# ADK_MEGA_2560-REV3.net
KiCad netlist of a schematic drawn in EAGLE
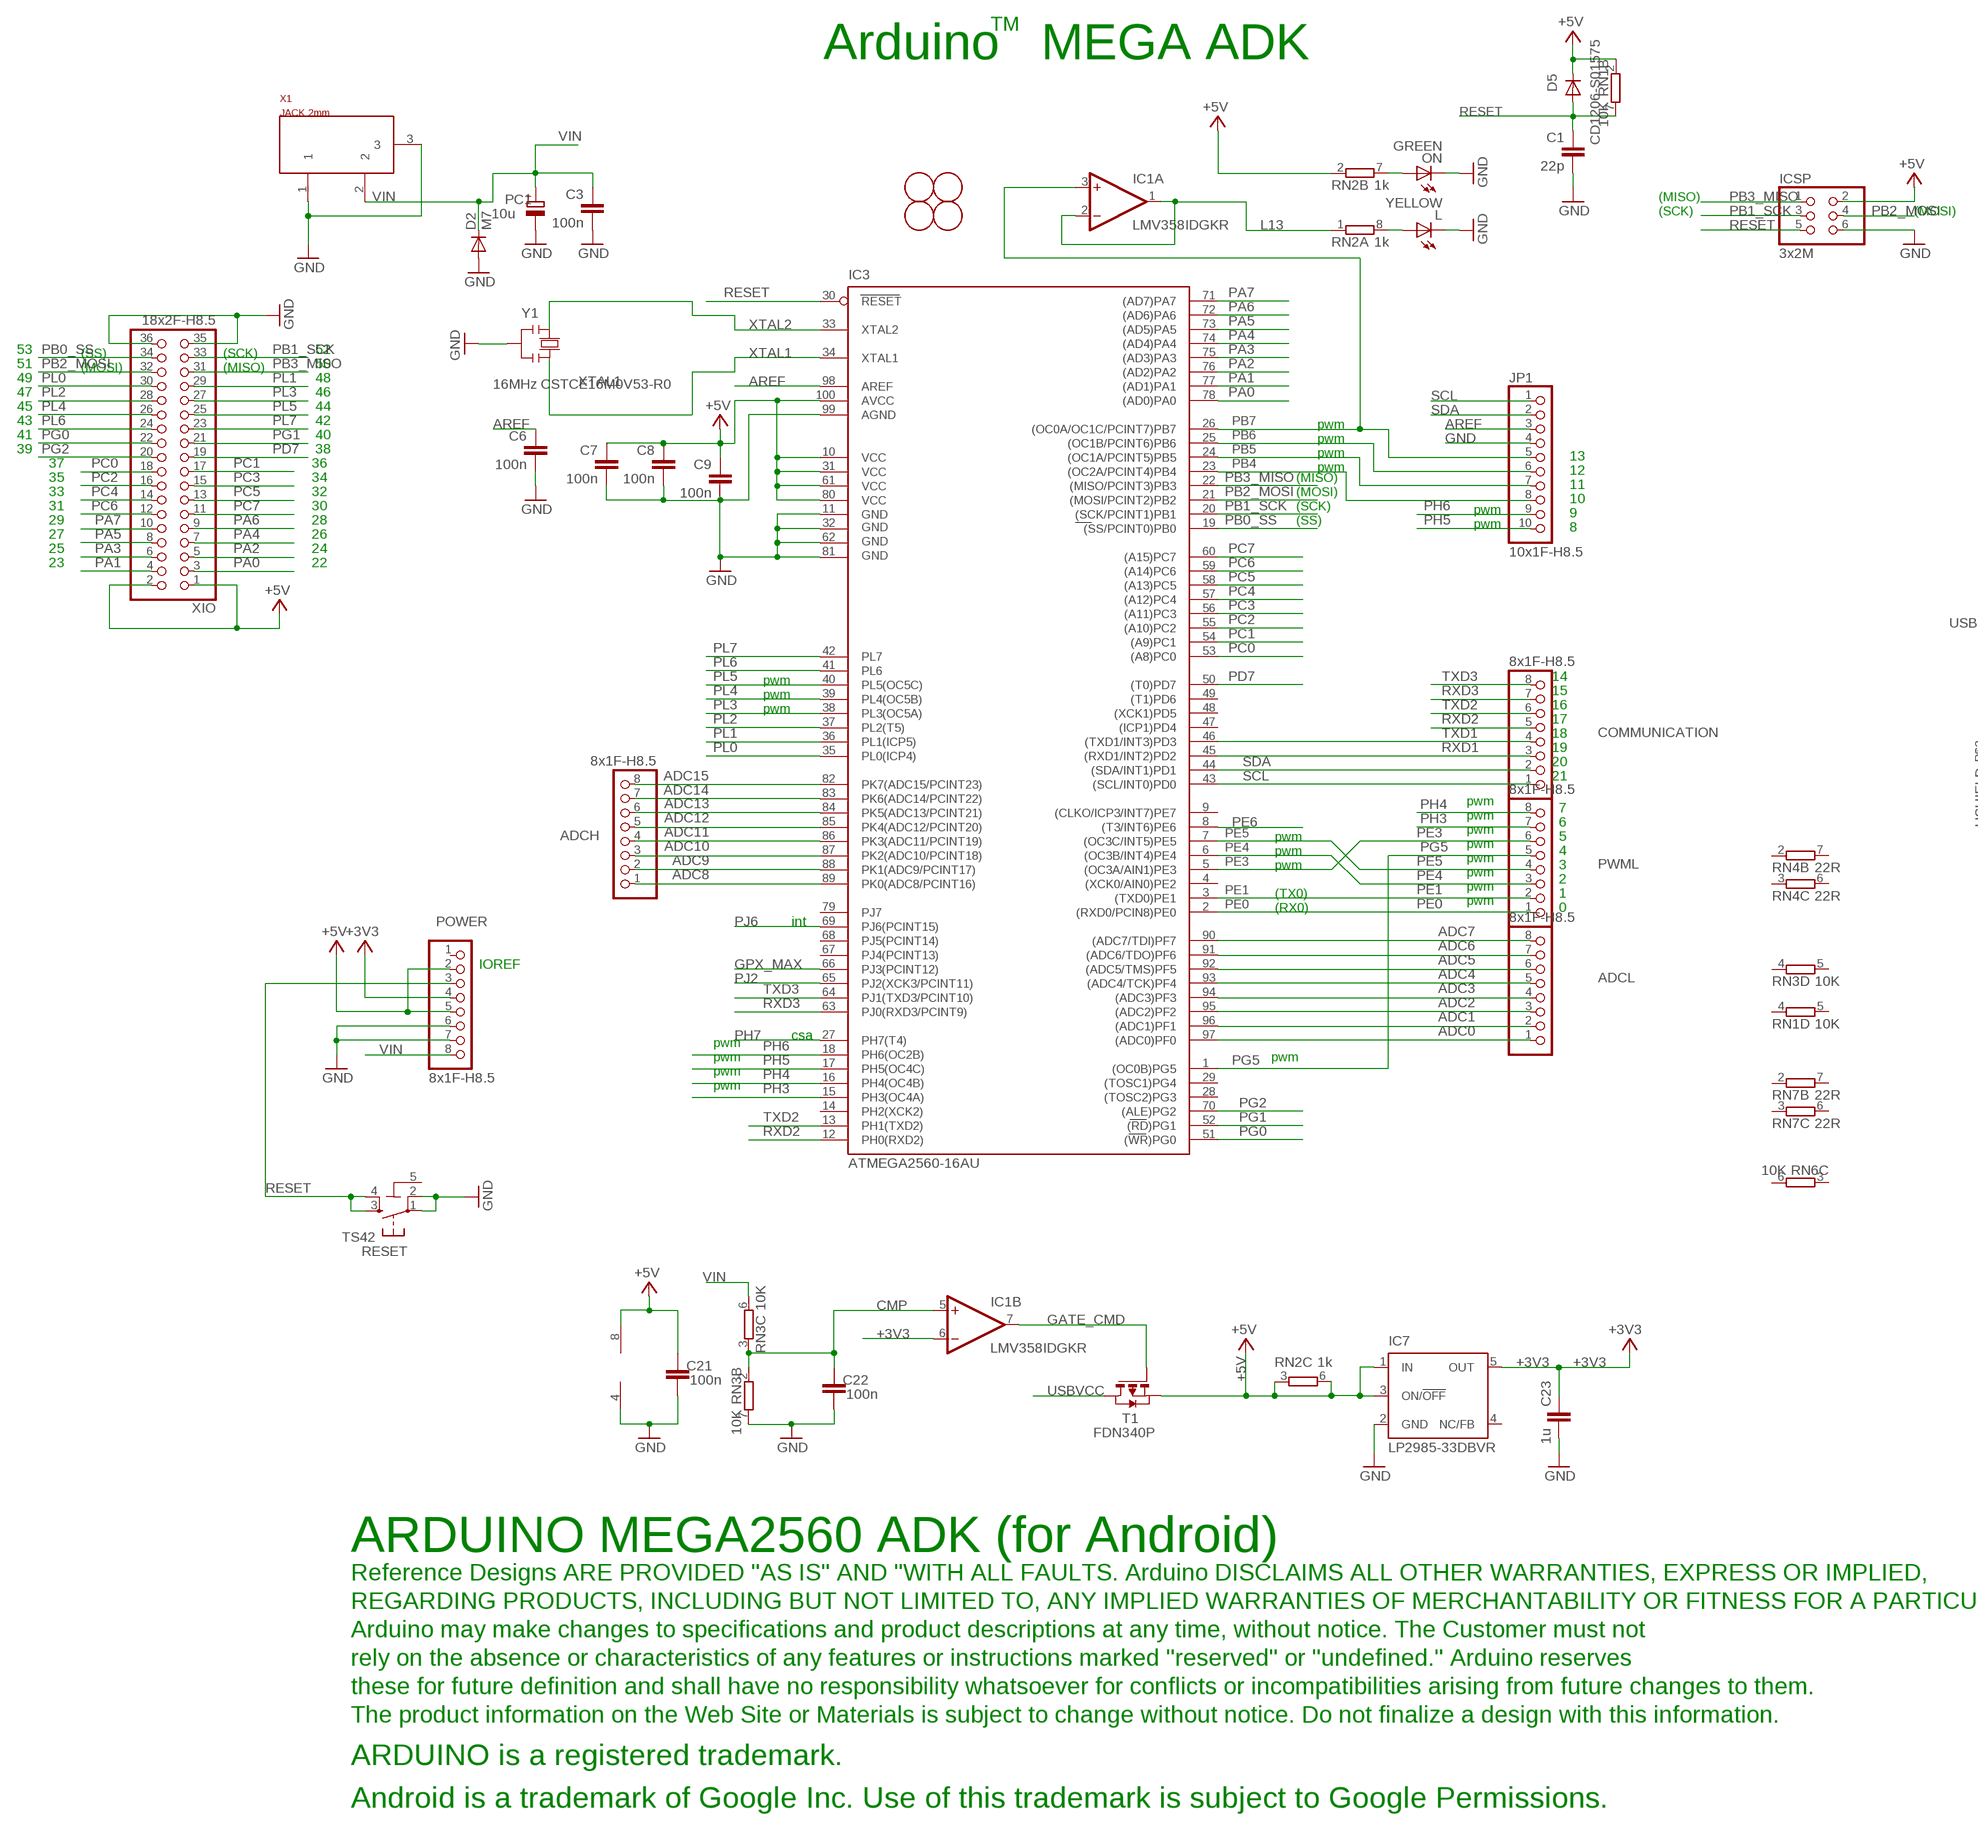
[diagram p0: schematic, sheet 1, part 1 of 2]
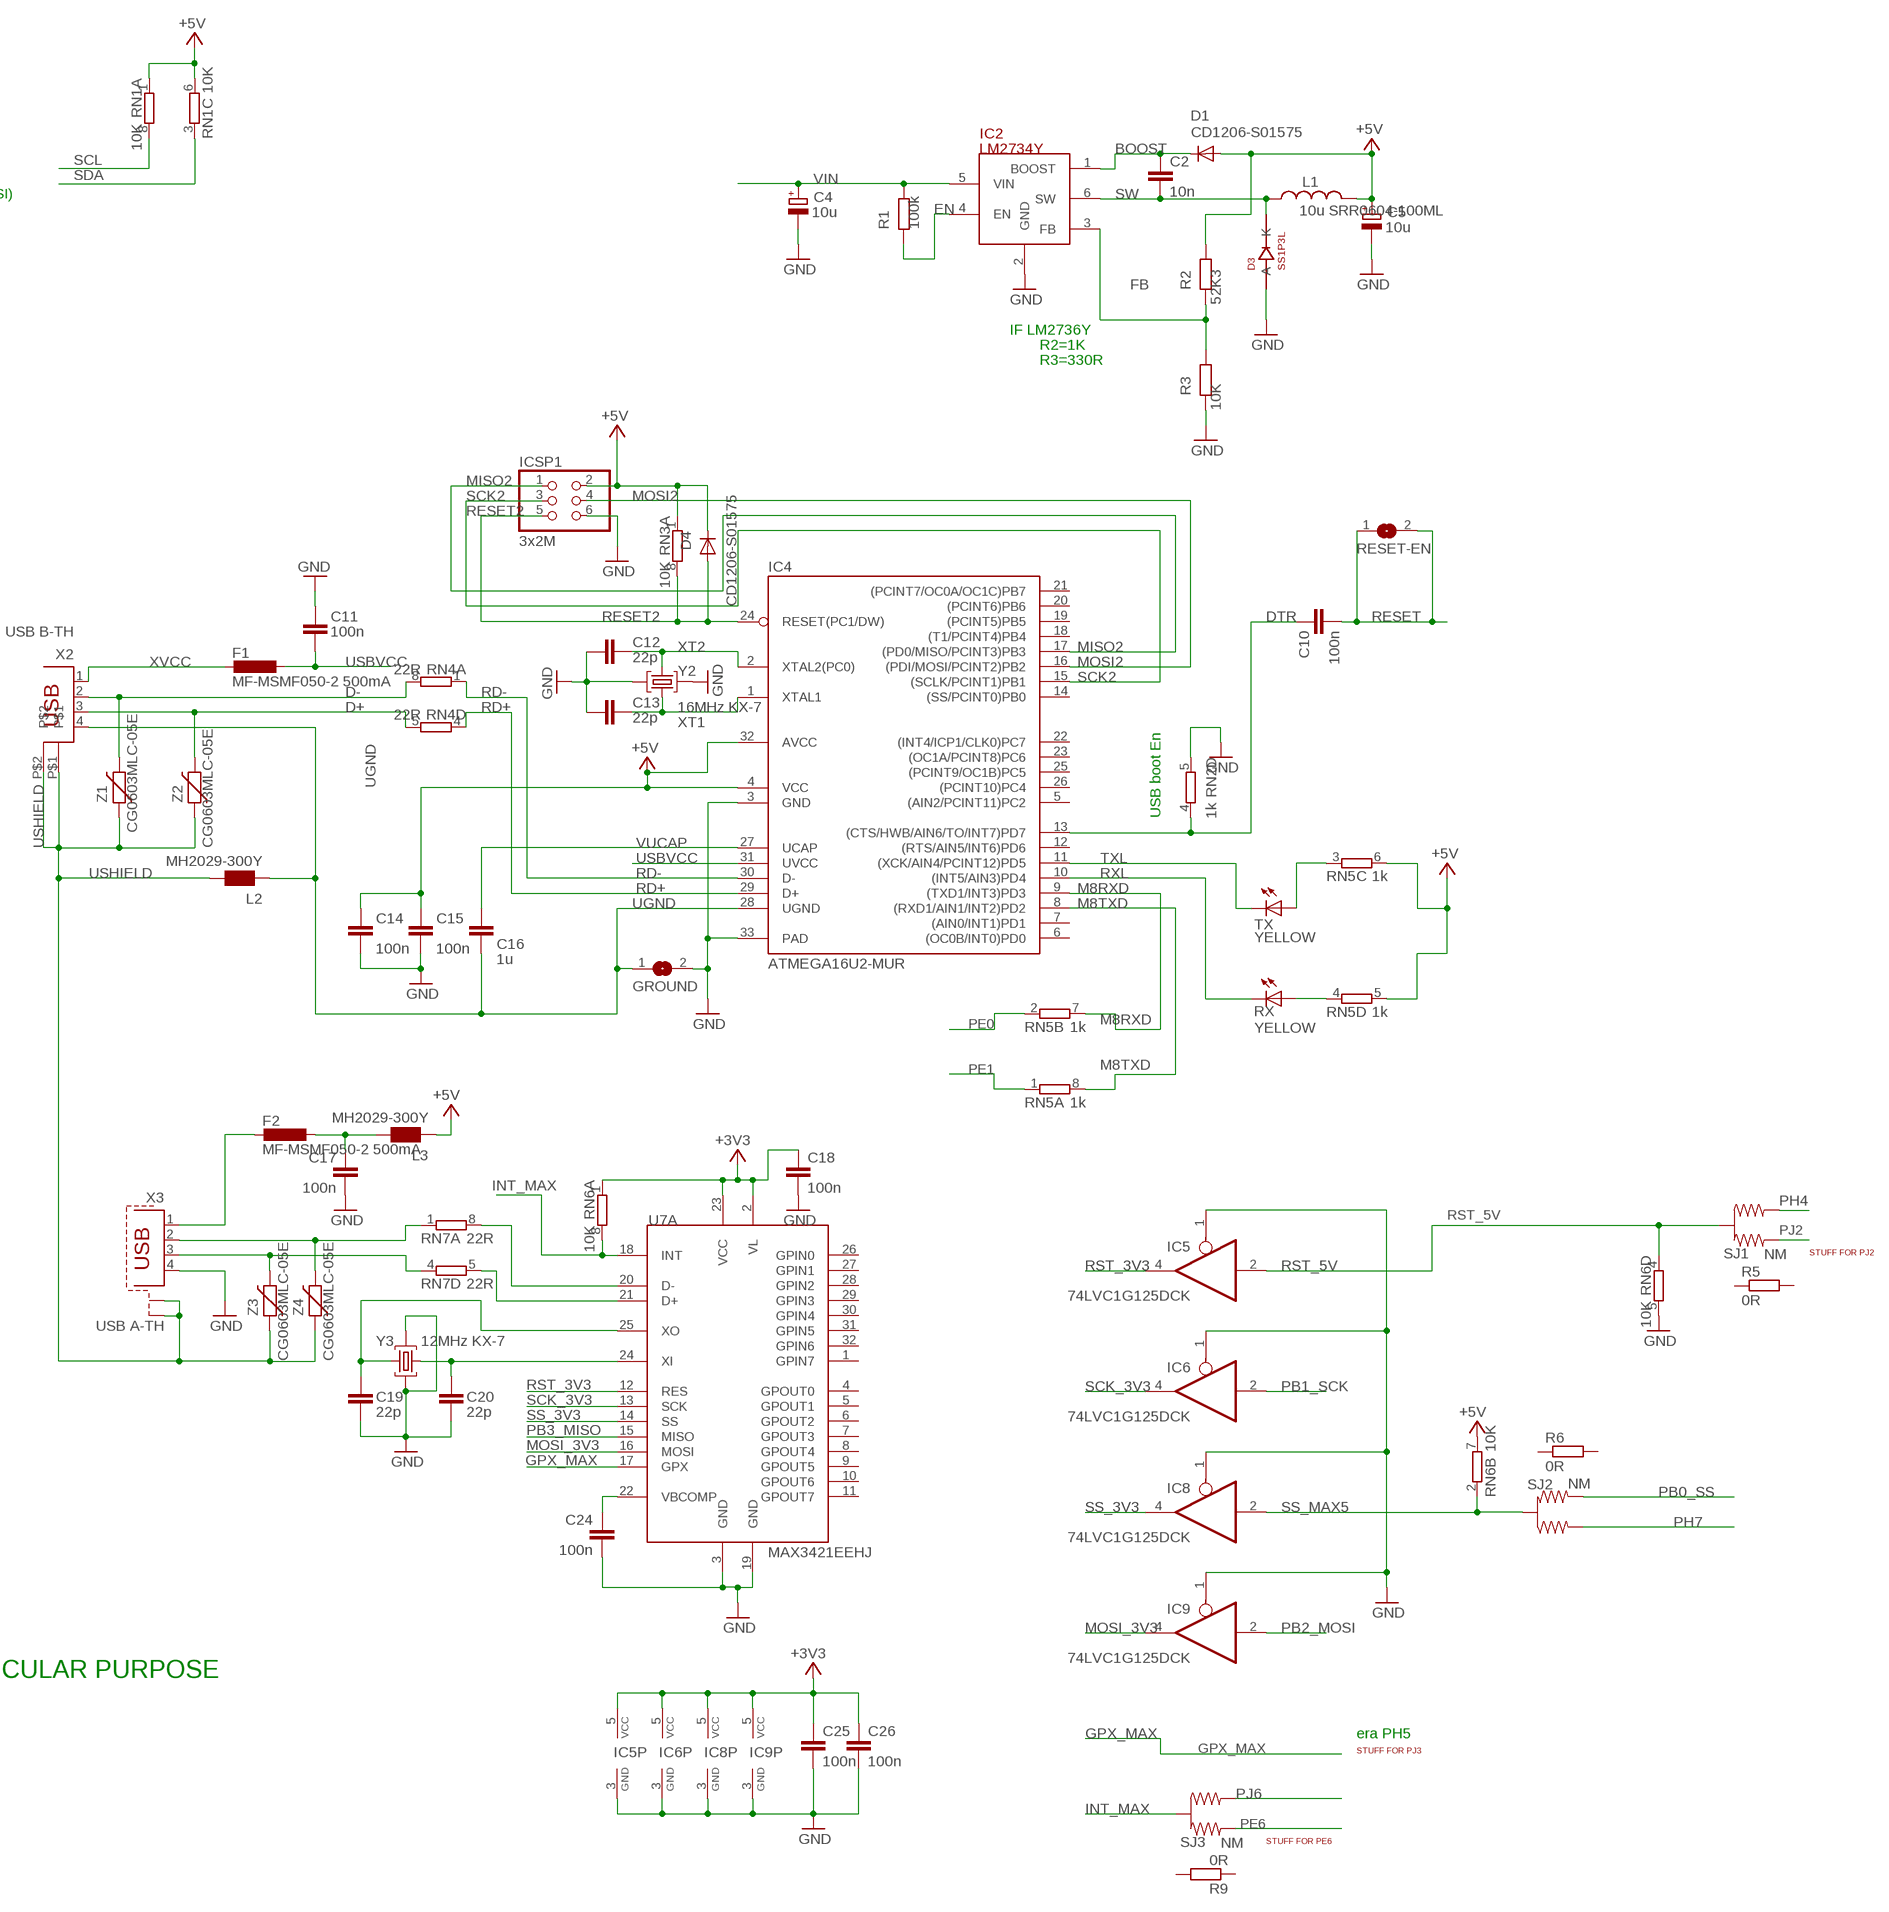
[diagram p1: schematic, sheet 1, part 2 of 2]

(export (version "E")
  (design (tool "Eeschema 10.0.6"))
  (components
    (comp (ref "ADCH")
      (value "8x1F-H8.5")
      (footprint "eagle-import:1X08")
      (libsource (lib "eagle-import") (part "PINHD-1X8"))
    )
    (comp (ref "ADCL")
      (value "8x1F-H8.5")
      (footprint "eagle-import:1X08")
      (libsource (lib "eagle-import") (part "PINHD-1X8"))
    )
    (comp (ref "C1")
      (value "22p")
      (footprint "eagle-import:C0603-ROUND")
      (libsource (lib "eagle-import") (part "C-EU0603-RND"))
    )
    (comp (ref "C2")
      (value "10n")
      (footprint "eagle-import:C0603-ROUND")
      (libsource (lib "eagle-import") (part "C-EUC0603"))
    )
    (comp (ref "C3")
      (value "100n")
      (footprint "eagle-import:C0603-ROUND")
      (libsource (lib "eagle-import") (part "C-EU0603-RND"))
    )
    (comp (ref "C4")
      (value "10u")
      (footprint "eagle-import:SMC_B")
      (libsource (lib "eagle-import") (part "CPOL-EUSMCB"))
    )
    (comp (ref "C5")
      (value "10u")
      (footprint "eagle-import:SMC_B")
      (libsource (lib "eagle-import") (part "CPOL-EUSMCB"))
    )
    (comp (ref "C6")
      (value "100n")
      (footprint "eagle-import:C0603-ROUND")
      (libsource (lib "eagle-import") (part "C-EU0603-RND"))
    )
    (comp (ref "C7")
      (value "100n")
      (footprint "eagle-import:C0603-ROUND")
      (libsource (lib "eagle-import") (part "C-EU0603-RND"))
    )
    (comp (ref "C8")
      (value "100n")
      (footprint "eagle-import:C0603-ROUND")
      (libsource (lib "eagle-import") (part "C-EU0603-RND"))
    )
    (comp (ref "C9")
      (value "100n")
      (footprint "eagle-import:C0603-ROUND")
      (libsource (lib "eagle-import") (part "C-EU0603-RND"))
    )
    (comp (ref "C10")
      (value "100n")
      (footprint "eagle-import:C0603-ROUND")
      (libsource (lib "eagle-import") (part "C-EU0603-RND"))
    )
    (comp (ref "C11")
      (value "100n")
      (footprint "eagle-import:C0603-ROUND")
      (libsource (lib "eagle-import") (part "C-EU0603-RND"))
    )
    (comp (ref "C12")
      (value "22p")
      (footprint "eagle-import:C0603-ROUND")
      (libsource (lib "eagle-import") (part "C-EU0603-RND"))
    )
    (comp (ref "C13")
      (value "22p")
      (footprint "eagle-import:C0603-ROUND")
      (libsource (lib "eagle-import") (part "C-EU0603-RND"))
    )
    (comp (ref "C14")
      (value "100n")
      (footprint "eagle-import:C0603-ROUND")
      (libsource (lib "eagle-import") (part "C-EU0603-RND"))
    )
    (comp (ref "C15")
      (value "100n")
      (footprint "eagle-import:C0603-ROUND")
      (libsource (lib "eagle-import") (part "C-EU0603-RND"))
    )
    (comp (ref "C16")
      (value "1u")
      (footprint "eagle-import:C0603-ROUND")
      (libsource (lib "eagle-import") (part "C-EU0603-RND"))
    )
    (comp (ref "C17")
      (value "100n")
      (footprint "eagle-import:C0603-ROUND")
      (libsource (lib "eagle-import") (part "C-EU0603-RND"))
    )
    (comp (ref "C18")
      (value "100n")
      (footprint "eagle-import:C0603-ROUND")
      (libsource (lib "eagle-import") (part "C-EU0603-RND"))
    )
    (comp (ref "C19")
      (value "22p")
      (footprint "eagle-import:C0603-ROUND")
      (libsource (lib "eagle-import") (part "C-EU0603-RND"))
    )
    (comp (ref "C20")
      (value "22p")
      (footprint "eagle-import:C0603-ROUND")
      (libsource (lib "eagle-import") (part "C-EU0603-RND"))
    )
    (comp (ref "C21")
      (value "100n")
      (footprint "eagle-import:C0603-ROUND")
      (libsource (lib "eagle-import") (part "C-EU0603-RND"))
    )
    (comp (ref "C22")
      (value "100n")
      (footprint "eagle-import:C0603-ROUND")
      (libsource (lib "eagle-import") (part "C-EU0603-RND"))
    )
    (comp (ref "C23")
      (value "1u")
      (footprint "eagle-import:C0603-ROUND")
      (libsource (lib "eagle-import") (part "C-EU0603-RND"))
    )
    (comp (ref "C24")
      (value "100n")
      (footprint "eagle-import:C0603-ROUND")
      (libsource (lib "eagle-import") (part "C-EU0603-RND"))
    )
    (comp (ref "C25")
      (value "100n")
      (footprint "eagle-import:C0603-ROUND")
      (libsource (lib "eagle-import") (part "C-EU0603-RND"))
    )
    (comp (ref "C26")
      (value "100n")
      (footprint "eagle-import:C0603-ROUND")
      (libsource (lib "eagle-import") (part "C-EU0603-RND"))
    )
    (comp (ref "COMMUNICATION")
      (value "8x1F-H8.5")
      (footprint "eagle-import:1X08")
      (libsource (lib "eagle-import") (part "PINHD-1X8"))
    )
    (comp (ref "D1")
      (value "CD1206-S01575")
      (footprint "eagle-import:MINIMELF")
      (libsource (lib "eagle-import") (part "DIODE-MINIMELF"))
    )
    (comp (ref "D2")
      (value "M7")
      (footprint "eagle-import:SMB")
      (libsource (lib "eagle-import") (part "DIODE-SMB"))
    )
    (comp (ref "D3")
      (value "SS1P3L")
      (footprint "eagle-import:DO220AAL")
      (libsource (lib "eagle-import") (part "SS1P3L"))
    )
    (comp (ref "D4")
      (value "CD1206-S01575")
      (footprint "eagle-import:MINIMELF")
      (libsource (lib "eagle-import") (part "DIODE-MINIMELF"))
    )
    (comp (ref "D5")
      (value "CD1206-S01575")
      (footprint "eagle-import:MINIMELF")
      (libsource (lib "eagle-import") (part "DIODE-MINIMELF"))
    )
    (comp (ref "F1")
      (value "MF-MSMF050-2 500mA")
      (footprint "eagle-import:L1812")
      (libsource (lib "eagle-import") (part "L-EUL1812"))
    )
    (comp (ref "F2")
      (value "MF-MSMF050-2 500mA")
      (footprint "eagle-import:L1812")
      (libsource (lib "eagle-import") (part "L-EUL1812"))
    )
    (comp (ref "FID1")
      (value "FIDUCIALMOUNT")
      (footprint "eagle-import:FIDUCIA-MOUNT")
      (libsource (lib "eagle-import") (part "FIDUCIALMOUNT"))
    )
    (comp (ref "FID2")
      (value "FIDUCIALMOUNT")
      (footprint "eagle-import:FIDUCIA-MOUNT")
      (libsource (lib "eagle-import") (part "FIDUCIALMOUNT"))
    )
    (comp (ref "FID3")
      (value "FIDUCIALMOUNT")
      (footprint "eagle-import:FIDUCIA-MOUNT")
      (libsource (lib "eagle-import") (part "FIDUCIALMOUNT"))
    )
    (comp (ref "FID4")
      (value "FIDUCIALMOUNT")
      (footprint "eagle-import:FIDUCIA-MOUNT")
      (libsource (lib "eagle-import") (part "FIDUCIALMOUNT"))
    )
    (comp (ref "GROUND")
      (value "SJ")
      (footprint "eagle-import:SJ")
      (libsource (lib "eagle-import") (part "SJ"))
    )
    (comp (ref "IC1")
      (value "LMV358IDGKR")
      (footprint "eagle-import:MSOP08")
      (libsource (lib "eagle-import") (part "LMV358?MMX"))
    )
    (comp (ref "IC2")
      (value "LM2734Y")
      (footprint "eagle-import:SOT23-6")
      (libsource (lib "eagle-import") (part "LM2736Y"))
    )
    (comp (ref "IC3")
      (value "ATMEGA2560-16AU")
      (footprint "eagle-import:TQFP100")
      (libsource (lib "eagle-import") (part "ATMEGA2560AU2560-16"))
    )
    (comp (ref "IC4")
      (value "ATMEGA16U2-MUR")
      (footprint "eagle-import:MLF32")
      (libsource (lib "eagle-import") (part "ATMEGA16U2-MU"))
    )
    (comp (ref "IC5")
      (value "74LVC1G125DCK")
      (footprint "eagle-import:SC70-5")
      (libsource (lib "eagle-import") (part "741G125DCKLVC"))
    )
    (comp (ref "IC6")
      (value "74LVC1G125DCK")
      (footprint "eagle-import:SC70-5")
      (libsource (lib "eagle-import") (part "741G125DCKLVC"))
    )
    (comp (ref "IC7")
      (value "LP2985-33DBVR")
      (footprint "eagle-import:SOT23-DBV")
      (libsource (lib "eagle-import") (part "LP2985-XXDBVR33"))
    )
    (comp (ref "IC8")
      (value "74LVC1G125DCK")
      (footprint "eagle-import:SC70-5")
      (libsource (lib "eagle-import") (part "741G125DCKLVC"))
    )
    (comp (ref "IC9")
      (value "74LVC1G125DCK")
      (footprint "eagle-import:SC70-5")
      (libsource (lib "eagle-import") (part "741G125DCKLVC"))
    )
    (comp (ref "ICSP")
      (value "3x2M")
      (footprint "eagle-import:2X03")
      (libsource (lib "eagle-import") (part "PINHD-2X3"))
    )
    (comp (ref "ICSP1")
      (value "3x2M")
      (footprint "eagle-import:2X03")
      (libsource (lib "eagle-import") (part "PINHD-2X3"))
    )
    (comp (ref "JP1")
      (value "10x1F-H8.5")
      (footprint "eagle-import:1X10")
      (libsource (lib "eagle-import") (part "PINHD-1X10"))
    )
    (comp (ref "L")
      (value "YELLOW")
      (footprint "eagle-import:CHIP-LED0805")
      (libsource (lib "eagle-import") (part "LEDCHIP-LED0805"))
    )
    (comp (ref "L1")
      (value "10u SRR0604-100ML")
      (footprint "eagle-import:SRR0604")
      (libsource (lib "eagle-import") (part "L-USSRR0604"))
    )
    (comp (ref "L2")
      (value "MH2029-300Y")
      (footprint "eagle-import:0805")
      (libsource (lib "eagle-import") (part "WE-CBF_0805"))
    )
    (comp (ref "L3")
      (value "MH2029-300Y")
      (footprint "eagle-import:0805")
      (libsource (lib "eagle-import") (part "WE-CBF_0805"))
    )
    (comp (ref "ON")
      (value "GREEN")
      (footprint "eagle-import:CHIP-LED0805")
      (libsource (lib "eagle-import") (part "LEDCHIP-LED0805"))
    )
    (comp (ref "PC1")
      (value "10u")
      (footprint "eagle-import:SMC_B")
      (libsource (lib "eagle-import") (part "CPOL-EUSMCB"))
    )
    (comp (ref "POWER")
      (value "8x1F-H8.5")
      (footprint "eagle-import:1X08")
      (libsource (lib "eagle-import") (part "PINHD-1X8"))
    )
    (comp (ref "PWML")
      (value "8x1F-H8.5")
      (footprint "eagle-import:1X08")
      (libsource (lib "eagle-import") (part "PINHD-1X8"))
    )
    (comp (ref "R1")
      (value "100k")
      (footprint "eagle-import:R0603-ROUND")
      (libsource (lib "eagle-import") (part "R-EU_0603-RND"))
    )
    (comp (ref "R2")
      (value "52K3")
      (footprint "eagle-import:R0603-ROUND")
      (libsource (lib "eagle-import") (part "R-EU_0603-RND"))
    )
    (comp (ref "R3")
      (value "10K")
      (footprint "eagle-import:R0603-ROUND")
      (libsource (lib "eagle-import") (part "R-EU_0603-RND"))
    )
    (comp (ref "R5")
      (value "0R")
      (footprint "eagle-import:R0402")
      (libsource (lib "eagle-import") (part "R-EU_R0402"))
    )
    (comp (ref "R6")
      (value "0R")
      (footprint "eagle-import:R0402")
      (libsource (lib "eagle-import") (part "R-EU_R0402"))
    )
    (comp (ref "R9")
      (value "0R")
      (footprint "eagle-import:R0402")
      (libsource (lib "eagle-import") (part "R-EU_R0402"))
    )
    (comp (ref "RESET")
      (value "TS42")
      (footprint "eagle-import:TS42")
      (libsource (lib "eagle-import") (part "TS42"))
    )
    (comp (ref "RESET-EN")
      (value "SJ")
      (footprint "eagle-import:SJ")
      (libsource (lib "eagle-import") (part "SJ"))
    )
    (comp (ref "RN1")
      (value "10K")
      (footprint "eagle-import:CAT16")
      (libsource (lib "eagle-import") (part "4R-NCAT16"))
    )
    (comp (ref "RN2")
      (value "1k")
      (footprint "eagle-import:CAY16")
      (libsource (lib "eagle-import") (part "4R-NCAY16"))
    )
    (comp (ref "RN3")
      (value "10K")
      (footprint "eagle-import:CAT16")
      (libsource (lib "eagle-import") (part "4R-NCAT16"))
    )
    (comp (ref "RN4")
      (value "22R")
      (footprint "eagle-import:CAY16")
      (libsource (lib "eagle-import") (part "4R-NCAY16"))
    )
    (comp (ref "RN5")
      (value "1k")
      (footprint "eagle-import:CAY16")
      (libsource (lib "eagle-import") (part "4R-NCAY16"))
    )
    (comp (ref "RN6")
      (value "10K")
      (footprint "eagle-import:CAT16")
      (libsource (lib "eagle-import") (part "4R-NCAT16"))
    )
    (comp (ref "RN7")
      (value "22R")
      (footprint "eagle-import:CAY16")
      (libsource (lib "eagle-import") (part "4R-NCAY16"))
    )
    (comp (ref "RX")
      (value "YELLOW")
      (footprint "eagle-import:CHIP-LED0805")
      (libsource (lib "eagle-import") (part "LEDCHIP-LED0805"))
    )
    (comp (ref "SJ1")
      (value "NM")
      (footprint "eagle-import:J0402")
      (libsource (lib "eagle-import") (part "J0402"))
    )
    (comp (ref "SJ2")
      (value "NM")
      (footprint "eagle-import:J0402")
      (libsource (lib "eagle-import") (part "J0402"))
    )
    (comp (ref "SJ3")
      (value "NM")
      (footprint "eagle-import:J0402")
      (libsource (lib "eagle-import") (part "J0402"))
    )
    (comp (ref "T1")
      (value "FDN340P")
      (footprint "eagle-import:SOT-23")
      (libsource (lib "eagle-import") (part "PMOSSOT23"))
    )
    (comp (ref "TX")
      (value "YELLOW")
      (footprint "eagle-import:CHIP-LED0805")
      (libsource (lib "eagle-import") (part "LEDCHIP-LED0805"))
    )
    (comp (ref "U7A")
      (value "MAX3421EEHJ")
      (footprint "eagle-import:TQFP32-05")
      (libsource (lib "eagle-import") (part "MAX3421EEHJ"))
    )
    (comp (ref "X1")
      (value "JACK 2mm")
      (footprint "eagle-import:POWERSUPPLY_DC-21MM")
      (libsource (lib "eagle-import") (part "POWERSUPPLY_DC21MMX"))
    )
    (comp (ref "X2")
      (value "USB B-TH")
      (footprint "eagle-import:PN61729")
      (libsource (lib "eagle-import") (part "PN61729"))
    )
    (comp (ref "X3")
      (value "USB A-TH")
      (footprint "eagle-import:PN87520-S")
      (libsource (lib "eagle-import") (part "PN87520-S"))
    )
    (comp (ref "XIO")
      (value "18x2F-H8.5")
      (footprint "eagle-import:2X18")
      (libsource (lib "eagle-import") (part "PINHD-2X18"))
    )
    (comp (ref "Y1")
      (value "16MHz CSTCE16M0V53-R0")
      (footprint "eagle-import:RESONATOR")
      (libsource (lib "eagle-import") (part "RESONATORMU"))
    )
    (comp (ref "Y2")
      (value "16MHz KX-7")
      (footprint "eagle-import:CRYSTAL-3.2-2.5")
      (libsource (lib "eagle-import") (part "CRYSTAL-3.2-2.5"))
    )
    (comp (ref "Y3")
      (value "12MHz KX-7")
      (footprint "eagle-import:CRYSTAL-3.2-2.5")
      (libsource (lib "eagle-import") (part "CRYSTAL-3.2-2.5"))
    )
    (comp (ref "Z1")
      (value "CG0603MLC-05E")
      (footprint "eagle-import:CT_CN0603")
      (libsource (lib "eagle-import") (part "VARISTORCN0603"))
    )
    (comp (ref "Z2")
      (value "CG0603MLC-05E")
      (footprint "eagle-import:CT_CN0603")
      (libsource (lib "eagle-import") (part "VARISTORCN0603"))
    )
    (comp (ref "Z3")
      (value "CG0603MLC-05E")
      (footprint "eagle-import:CT_CN0603")
      (libsource (lib "eagle-import") (part "VARISTORCN0603"))
    )
    (comp (ref "Z4")
      (value "CG0603MLC-05E")
      (footprint "eagle-import:CT_CN0603")
      (libsource (lib "eagle-import") (part "VARISTORCN0603"))
    )
  )
  (nets
    (net (code "1") (name "+3V3") (class "Default")
      (node (ref "C18") (pin "1") (pinfunction "1_1") (pintype "passive"))
      (node (ref "C23") (pin "2") (pinfunction "2_2") (pintype "passive"))
      (node (ref "C25") (pin "1") (pinfunction "1_1") (pintype "passive"))
      (node (ref "C26") (pin "1") (pinfunction "1_1") (pintype "passive"))
      (node (ref "IC1") (pin "6") (pinfunction "-IN_6") (pintype "input"))
      (node (ref "IC5") (pin "5") (pinfunction "VCC_5") (pintype "power_in"))
      (node (ref "IC6") (pin "5") (pinfunction "VCC_5") (pintype "power_in"))
      (node (ref "IC7") (pin "5") (pinfunction "OUT_5") (pintype "passive"))
      (node (ref "IC8") (pin "5") (pinfunction "VCC_5") (pintype "power_in"))
      (node (ref "IC9") (pin "5") (pinfunction "VCC_5") (pintype "power_in"))
      (node (ref "POWER") (pin "4") (pinfunction "4_4") (pintype "passive"))
      (node (ref "RN6") (pin "1") (pinfunction "1_1") (pintype "passive"))
      (node (ref "U7A") (pin "2") (pinfunction "VL_2") (pintype "bidirectional"))
      (node (ref "U7A") (pin "23") (pinfunction "VCC_23") (pintype "bidirectional"))
    )
    (net (code "2") (name "+5V") (class "Default")
      (node (ref "C14") (pin "1") (pinfunction "1_1") (pintype "passive"))
      (node (ref "C15") (pin "1") (pinfunction "1_1") (pintype "passive"))
      (node (ref "C21") (pin "2") (pinfunction "2_2") (pintype "passive"))
      (node (ref "C5") (pin "+") (pinfunction "+_+") (pintype "passive"))
      (node (ref "C7") (pin "1") (pinfunction "1_1") (pintype "passive"))
      (node (ref "C8") (pin "1") (pinfunction "1_1") (pintype "passive"))
      (node (ref "C9") (pin "1") (pinfunction "1_1") (pintype "passive"))
      (node (ref "D1") (pin "A") (pinfunction "A_A") (pintype "passive"))
      (node (ref "D4") (pin "C") (pinfunction "C_C") (pintype "passive"))
      (node (ref "D5") (pin "C") (pinfunction "C_C") (pintype "passive"))
      (node (ref "IC1") (pin "8") (pinfunction "V+_8") (pintype "power_in"))
      (node (ref "IC3") (pin "10") (pinfunction "VCC_10") (pintype "power_in"))
      (node (ref "IC3") (pin "100") (pinfunction "AVCC_100") (pintype "power_in"))
      (node (ref "IC3") (pin "31") (pinfunction "VCC1_31") (pintype "power_in"))
      (node (ref "IC3") (pin "61") (pinfunction "VCC2_61") (pintype "power_in"))
      (node (ref "IC3") (pin "80") (pinfunction "VCC3_80") (pintype "power_in"))
      (node (ref "IC4") (pin "32") (pinfunction "AVCC_32") (pintype "power_in"))
      (node (ref "IC4") (pin "4") (pinfunction "VCC_4") (pintype "power_in"))
      (node (ref "IC7") (pin "1") (pinfunction "IN_1") (pintype "input"))
      (node (ref "IC7") (pin "3") (pinfunction "ON/~{OFF}_3") (pintype "input"))
      (node (ref "ICSP") (pin "2") (pinfunction "2_2") (pintype "passive"))
      (node (ref "ICSP1") (pin "2") (pinfunction "2_2") (pintype "passive"))
      (node (ref "L1") (pin "P$2") (pinfunction "2_P$2") (pintype "passive"))
      (node (ref "L3") (pin "1") (pinfunction "1_1") (pintype "passive"))
      (node (ref "POWER") (pin "2") (pinfunction "2_2") (pintype "passive"))
      (node (ref "POWER") (pin "5") (pinfunction "5_5") (pintype "passive"))
      (node (ref "R2") (pin "1") (pinfunction "1_1") (pintype "passive"))
      (node (ref "RN1") (pin "1") (pinfunction "1_1") (pintype "passive"))
      (node (ref "RN1") (pin "2") (pinfunction "1_2") (pintype "passive"))
      (node (ref "RN1") (pin "6") (pinfunction "2_6") (pintype "passive"))
      (node (ref "RN2") (pin "2") (pinfunction "1_2") (pintype "passive"))
      (node (ref "RN2") (pin "3") (pinfunction "1_3") (pintype "passive"))
      (node (ref "RN2") (pin "6") (pinfunction "2_6") (pintype "passive"))
      (node (ref "RN3") (pin "1") (pinfunction "1_1") (pintype "passive"))
      (node (ref "RN5") (pin "5") (pinfunction "2_5") (pintype "passive"))
      (node (ref "RN5") (pin "6") (pinfunction "2_6") (pintype "passive"))
      (node (ref "RN6") (pin "7") (pinfunction "2_7") (pintype "passive"))
      (node (ref "T1") (pin "2") (pinfunction "S_2") (pintype "passive"))
      (node (ref "XIO") (pin "1") (pinfunction "1_1") (pintype "passive"))
      (node (ref "XIO") (pin "2") (pinfunction "2_2") (pintype "passive"))
    )
    (net (code "3") (name "/5-GND") (class "Default")
      (node (ref "RESET") (pin "5") (pinfunction "5-GND_5") (pintype "power_in"))
    )
    (net (code "4") (name "/ADC0") (class "Default")
      (node (ref "ADCL") (pin "1") (pinfunction "1_1") (pintype "passive"))
      (node (ref "IC3") (pin "97") (pinfunction "(ADC0)PF0_97") (pintype "bidirectional"))
    )
    (net (code "5") (name "/ADC1") (class "Default")
      (node (ref "ADCL") (pin "2") (pinfunction "2_2") (pintype "passive"))
      (node (ref "IC3") (pin "96") (pinfunction "(ADC1)PF1_96") (pintype "bidirectional"))
    )
    (net (code "6") (name "/ADC2") (class "Default")
      (node (ref "ADCL") (pin "3") (pinfunction "3_3") (pintype "passive"))
      (node (ref "IC3") (pin "95") (pinfunction "(ADC2)PF2_95") (pintype "bidirectional"))
    )
    (net (code "7") (name "/ADC3") (class "Default")
      (node (ref "ADCL") (pin "4") (pinfunction "4_4") (pintype "passive"))
      (node (ref "IC3") (pin "94") (pinfunction "(ADC3)PF3_94") (pintype "bidirectional"))
    )
    (net (code "8") (name "/ADC4") (class "Default")
      (node (ref "ADCL") (pin "5") (pinfunction "5_5") (pintype "passive"))
      (node (ref "IC3") (pin "93") (pinfunction "(ADC4/TCK)PF4_93") (pintype "bidirectional"))
    )
    (net (code "9") (name "/ADC5") (class "Default")
      (node (ref "ADCL") (pin "6") (pinfunction "6_6") (pintype "passive"))
      (node (ref "IC3") (pin "92") (pinfunction "(ADC5/TMS)PF5_92") (pintype "bidirectional"))
    )
    (net (code "10") (name "/ADC6") (class "Default")
      (node (ref "ADCL") (pin "7") (pinfunction "7_7") (pintype "passive"))
      (node (ref "IC3") (pin "91") (pinfunction "(ADC6/TDO)PF6_91") (pintype "bidirectional"))
    )
    (net (code "11") (name "/ADC7") (class "Default")
      (node (ref "ADCL") (pin "8") (pinfunction "8_8") (pintype "passive"))
      (node (ref "IC3") (pin "90") (pinfunction "(ADC7/TDI)PF7_90") (pintype "bidirectional"))
    )
    (net (code "12") (name "/ADC8") (class "Default")
      (node (ref "ADCH") (pin "1") (pinfunction "1_1") (pintype "passive"))
      (node (ref "IC3") (pin "89") (pinfunction "PK0(ADC8/PCINT16)_89") (pintype "bidirectional"))
    )
    (net (code "13") (name "/ADC9") (class "Default")
      (node (ref "ADCH") (pin "2") (pinfunction "2_2") (pintype "passive"))
      (node (ref "IC3") (pin "88") (pinfunction "PK1(ADC9/PCINT17)_88") (pintype "bidirectional"))
    )
    (net (code "14") (name "/ADC10") (class "Default")
      (node (ref "ADCH") (pin "3") (pinfunction "3_3") (pintype "passive"))
      (node (ref "IC3") (pin "87") (pinfunction "PK2(ADC10/PCINT18)_87") (pintype "bidirectional"))
    )
    (net (code "15") (name "/ADC11") (class "Default")
      (node (ref "ADCH") (pin "4") (pinfunction "4_4") (pintype "passive"))
      (node (ref "IC3") (pin "86") (pinfunction "PK3(ADC11/PCINT19)_86") (pintype "bidirectional"))
    )
    (net (code "16") (name "/ADC12") (class "Default")
      (node (ref "ADCH") (pin "5") (pinfunction "5_5") (pintype "passive"))
      (node (ref "IC3") (pin "85") (pinfunction "PK4(ADC12/PCINT20)_85") (pintype "bidirectional"))
    )
    (net (code "17") (name "/ADC13") (class "Default")
      (node (ref "ADCH") (pin "6") (pinfunction "6_6") (pintype "passive"))
      (node (ref "IC3") (pin "84") (pinfunction "PK5(ADC13/PCINT21)_84") (pintype "bidirectional"))
    )
    (net (code "18") (name "/ADC14") (class "Default")
      (node (ref "ADCH") (pin "7") (pinfunction "7_7") (pintype "passive"))
      (node (ref "IC3") (pin "83") (pinfunction "PK6(ADC14/PCINT22)_83") (pintype "bidirectional"))
    )
    (net (code "19") (name "/ADC15") (class "Default")
      (node (ref "ADCH") (pin "8") (pinfunction "8_8") (pintype "passive"))
      (node (ref "IC3") (pin "82") (pinfunction "PK7(ADC15/PCINT23)_82") (pintype "bidirectional"))
    )
    (net (code "20") (name "/AREF") (class "Default")
      (node (ref "C6") (pin "1") (pinfunction "1_1") (pintype "passive"))
      (node (ref "IC3") (pin "98") (pinfunction "AREF_98") (pintype "bidirectional"))
      (node (ref "JP1") (pin "3") (pinfunction "3_3") (pintype "passive"))
    )
    (net (code "21") (name "/BOOST") (class "Default")
      (node (ref "C2") (pin "1") (pinfunction "1_1") (pintype "passive"))
      (node (ref "D1") (pin "C") (pinfunction "C_C") (pintype "passive"))
      (node (ref "IC2") (pin "1") (pinfunction "BOOST_1") (pintype "input"))
    )
    (net (code "22") (name "/CMP") (class "Default")
      (node (ref "C22") (pin "2") (pinfunction "2_2") (pintype "passive"))
      (node (ref "IC1") (pin "5") (pinfunction "+IN_5") (pintype "input"))
      (node (ref "RN3") (pin "2") (pinfunction "1_2") (pintype "passive"))
      (node (ref "RN3") (pin "3") (pinfunction "1_3") (pintype "passive"))
    )
    (net (code "23") (name "/D+") (class "Default")
      (node (ref "RN4") (pin "5") (pinfunction "2_5") (pintype "passive"))
      (node (ref "X2") (pin "3") (pinfunction "3_3") (pintype "bidirectional"))
      (node (ref "Z2") (pin "2") (pinfunction "2_2") (pintype "passive"))
    )
    (net (code "24") (name "/D-") (class "Default")
      (node (ref "RN4") (pin "8") (pinfunction "2_8") (pintype "passive"))
      (node (ref "X2") (pin "2") (pinfunction "2_2") (pintype "bidirectional"))
      (node (ref "Z1") (pin "2") (pinfunction "2_2") (pintype "passive"))
    )
    (net (code "25") (name "/DTR") (class "Default")
      (node (ref "C10") (pin "1") (pinfunction "1_1") (pintype "passive"))
      (node (ref "IC4") (pin "13") (pinfunction "(CTS/HWB/AIN6/TO/INT7)PD7_13") (pintype "bidirectional"))
      (node (ref "RN2") (pin "4") (pinfunction "1_4") (pintype "passive"))
    )
    (net (code "26") (name "/EN") (class "Default")
      (node (ref "IC2") (pin "4") (pinfunction "EN_4") (pintype "input"))
      (node (ref "R1") (pin "2") (pinfunction "2_2") (pintype "passive"))
    )
    (net (code "27") (name "/FB") (class "Default")
      (node (ref "IC2") (pin "3") (pinfunction "FB_3") (pintype "input"))
      (node (ref "R2") (pin "2") (pinfunction "2_2") (pintype "passive"))
      (node (ref "R3") (pin "1") (pinfunction "1_1") (pintype "passive"))
    )
    (net (code "28") (name "/GATE_CMD") (class "Default")
      (node (ref "IC1") (pin "7") (pinfunction "OUT_7") (pintype "output"))
      (node (ref "T1") (pin "3") (pinfunction "G_3") (pintype "passive"))
    )
    (net (code "29") (name "/GPX_MAX") (class "Default")
      (node (ref "IC3") (pin "66") (pinfunction "PJ3(PCINT12)_66") (pintype "bidirectional"))
      (node (ref "U7A") (pin "17") (pinfunction "GPX_17") (pintype "bidirectional"))
    )
    (net (code "30") (name "/INT_MAX") (class "Default")
      (node (ref "RN6") (pin "8") (pinfunction "2_8") (pintype "passive"))
      (node (ref "SJ3") (pin "2") (pinfunction "C_2") (pintype "passive"))
      (node (ref "U7A") (pin "18") (pinfunction "INT_18") (pintype "bidirectional"))
    )
    (net (code "31") (name "/L13") (class "Default")
      (node (ref "IC1") (pin "1") (pinfunction "OUT_1") (pintype "output"))
      (node (ref "IC1") (pin "2") (pinfunction "-IN_2") (pintype "input"))
      (node (ref "RN2") (pin "1") (pinfunction "1_1") (pintype "passive"))
    )
    (net (code "32") (name "/M8RXD") (class "Default")
      (node (ref "IC4") (pin "9") (pinfunction "(TXD1/INT3)PD3_9") (pintype "bidirectional"))
      (node (ref "RN5") (pin "7") (pinfunction "2_7") (pintype "passive"))
    )
    (net (code "33") (name "/M8TXD") (class "Default")
      (node (ref "IC4") (pin "8") (pinfunction "(RXD1/AIN1/INT2)PD2_8") (pintype "bidirectional"))
      (node (ref "RN5") (pin "8") (pinfunction "2_8") (pintype "passive"))
    )
    (net (code "34") (name "/MISO2") (class "Default")
      (node (ref "IC4") (pin "17") (pinfunction "(PD0/MISO/PCINT3)PB3_17") (pintype "bidirectional"))
      (node (ref "ICSP1") (pin "1") (pinfunction "1_1") (pintype "passive"))
    )
    (net (code "35") (name "/MOSI2") (class "Default")
      (node (ref "IC4") (pin "16") (pinfunction "(PDI/MOSI/PCINT2)PB2_16") (pintype "bidirectional"))
      (node (ref "ICSP1") (pin "4") (pinfunction "4_4") (pintype "passive"))
    )
    (net (code "36") (name "/MOSI_3V3") (class "Default")
      (node (ref "IC9") (pin "4") (pinfunction "O_4") (pintype "tri_state"))
      (node (ref "U7A") (pin "16") (pinfunction "MOSI_16") (pintype "bidirectional"))
    )
    (net (code "37") (name "/PA0") (class "Default")
      (node (ref "IC3") (pin "78") (pinfunction "(AD0)PA0_78") (pintype "bidirectional"))
      (node (ref "XIO") (pin "3") (pinfunction "3_3") (pintype "passive"))
    )
    (net (code "38") (name "/PA1") (class "Default")
      (node (ref "IC3") (pin "77") (pinfunction "(AD1)PA1_77") (pintype "bidirectional"))
      (node (ref "XIO") (pin "4") (pinfunction "4_4") (pintype "passive"))
    )
    (net (code "39") (name "/PA2") (class "Default")
      (node (ref "IC3") (pin "76") (pinfunction "(AD2)PA2_76") (pintype "bidirectional"))
      (node (ref "XIO") (pin "5") (pinfunction "5_5") (pintype "passive"))
    )
    (net (code "40") (name "/PA3") (class "Default")
      (node (ref "IC3") (pin "75") (pinfunction "(AD3)PA3_75") (pintype "bidirectional"))
      (node (ref "XIO") (pin "6") (pinfunction "6_6") (pintype "passive"))
    )
    (net (code "41") (name "/PA4") (class "Default")
      (node (ref "IC3") (pin "74") (pinfunction "(AD4)PA4_74") (pintype "bidirectional"))
      (node (ref "XIO") (pin "7") (pinfunction "7_7") (pintype "passive"))
    )
    (net (code "42") (name "/PA5") (class "Default")
      (node (ref "IC3") (pin "73") (pinfunction "(AD5)PA5_73") (pintype "bidirectional"))
      (node (ref "XIO") (pin "8") (pinfunction "8_8") (pintype "passive"))
    )
    (net (code "43") (name "/PA6") (class "Default")
      (node (ref "IC3") (pin "72") (pinfunction "(AD6)PA6_72") (pintype "bidirectional"))
      (node (ref "XIO") (pin "9") (pinfunction "9_9") (pintype "passive"))
    )
    (net (code "44") (name "/PA7") (class "Default")
      (node (ref "IC3") (pin "71") (pinfunction "(AD7)PA7_71") (pintype "bidirectional"))
      (node (ref "XIO") (pin "10") (pinfunction "10_10") (pintype "passive"))
    )
    (net (code "45") (name "/PB0_SS") (class "Default")
      (node (ref "IC3") (pin "19") (pinfunction "(SS/PCINT0)PB0_19") (pintype "bidirectional"))
      (node (ref "SJ2") (pin "3") (pinfunction "2_3") (pintype "passive"))
      (node (ref "XIO") (pin "34") (pinfunction "34_34") (pintype "passive"))
    )
    (net (code "46") (name "/PB1_SCK") (class "Default")
      (node (ref "IC3") (pin "20") (pinfunction "(SCK/PCINT1)PB1_20") (pintype "bidirectional"))
      (node (ref "IC6") (pin "2") (pinfunction "I_2") (pintype "input"))
      (node (ref "ICSP") (pin "3") (pinfunction "3_3") (pintype "passive"))
      (node (ref "XIO") (pin "33") (pinfunction "33_33") (pintype "passive"))
    )
    (net (code "47") (name "/PB2_MOSI") (class "Default")
      (node (ref "IC3") (pin "21") (pinfunction "(MOSI/PCINT2)PB2_21") (pintype "bidirectional"))
      (node (ref "IC9") (pin "2") (pinfunction "I_2") (pintype "input"))
      (node (ref "ICSP") (pin "4") (pinfunction "4_4") (pintype "passive"))
      (node (ref "XIO") (pin "32") (pinfunction "32_32") (pintype "passive"))
    )
    (net (code "48") (name "/PB3_MISO") (class "Default")
      (node (ref "IC3") (pin "22") (pinfunction "(MISO/PCINT3)PB3_22") (pintype "bidirectional"))
      (node (ref "ICSP") (pin "1") (pinfunction "1_1") (pintype "passive"))
      (node (ref "U7A") (pin "15") (pinfunction "MISO_15") (pintype "bidirectional"))
      (node (ref "XIO") (pin "31") (pinfunction "31_31") (pintype "passive"))
    )
    (net (code "49") (name "/PB4") (class "Default")
      (node (ref "IC3") (pin "23") (pinfunction "(OC2A/PCINT4)PB4_23") (pintype "bidirectional"))
      (node (ref "JP1") (pin "8") (pinfunction "8_8") (pintype "passive"))
    )
    (net (code "50") (name "/PB5") (class "Default")
      (node (ref "IC3") (pin "24") (pinfunction "(OC1A/PCINT5)PB5_24") (pintype "bidirectional"))
      (node (ref "JP1") (pin "7") (pinfunction "7_7") (pintype "passive"))
    )
    (net (code "51") (name "/PB6") (class "Default")
      (node (ref "IC3") (pin "25") (pinfunction "(OC1B/PCINT6)PB6_25") (pintype "bidirectional"))
      (node (ref "JP1") (pin "6") (pinfunction "6_6") (pintype "passive"))
    )
    (net (code "52") (name "/PB7") (class "Default")
      (node (ref "IC1") (pin "3") (pinfunction "+IN_3") (pintype "input"))
      (node (ref "IC3") (pin "26") (pinfunction "(OC0A/OC1C/PCINT7)PB7_26") (pintype "bidirectional"))
      (node (ref "JP1") (pin "5") (pinfunction "5_5") (pintype "passive"))
    )
    (net (code "53") (name "/PC0") (class "Default")
      (node (ref "IC3") (pin "53") (pinfunction "(A8)PC0_53") (pintype "bidirectional"))
      (node (ref "XIO") (pin "18") (pinfunction "18_18") (pintype "passive"))
    )
    (net (code "54") (name "/PC1") (class "Default")
      (node (ref "IC3") (pin "54") (pinfunction "(A9)PC1_54") (pintype "bidirectional"))
      (node (ref "XIO") (pin "17") (pinfunction "17_17") (pintype "passive"))
    )
    (net (code "55") (name "/PC2") (class "Default")
      (node (ref "IC3") (pin "55") (pinfunction "(A10)PC2_55") (pintype "bidirectional"))
      (node (ref "XIO") (pin "16") (pinfunction "16_16") (pintype "passive"))
    )
    (net (code "56") (name "/PC3") (class "Default")
      (node (ref "IC3") (pin "56") (pinfunction "(A11)PC3_56") (pintype "bidirectional"))
      (node (ref "XIO") (pin "15") (pinfunction "15_15") (pintype "passive"))
    )
    (net (code "57") (name "/PC4") (class "Default")
      (node (ref "IC3") (pin "57") (pinfunction "(A12)PC4_57") (pintype "bidirectional"))
      (node (ref "XIO") (pin "14") (pinfunction "14_14") (pintype "passive"))
    )
    (net (code "58") (name "/PC5") (class "Default")
      (node (ref "IC3") (pin "58") (pinfunction "(A13)PC5_58") (pintype "bidirectional"))
      (node (ref "XIO") (pin "13") (pinfunction "13_13") (pintype "passive"))
    )
    (net (code "59") (name "/PC6") (class "Default")
      (node (ref "IC3") (pin "59") (pinfunction "(A14)PC6_59") (pintype "bidirectional"))
      (node (ref "XIO") (pin "12") (pinfunction "12_12") (pintype "passive"))
    )
    (net (code "60") (name "/PC7") (class "Default")
      (node (ref "IC3") (pin "60") (pinfunction "(A15)PC7_60") (pintype "bidirectional"))
      (node (ref "XIO") (pin "11") (pinfunction "11_11") (pintype "passive"))
    )
    (net (code "61") (name "/PD7") (class "Default")
      (node (ref "IC3") (pin "50") (pinfunction "(T0)PD7_50") (pintype "bidirectional"))
      (node (ref "XIO") (pin "19") (pinfunction "19_19") (pintype "passive"))
    )
    (net (code "62") (name "/PE0") (class "Default")
      (node (ref "IC3") (pin "2") (pinfunction "(RXD0/PCIN8)PE0_2") (pintype "bidirectional"))
      (node (ref "PWML") (pin "1") (pinfunction "1_1") (pintype "passive"))
      (node (ref "RN5") (pin "2") (pinfunction "1_2") (pintype "passive"))
    )
    (net (code "63") (name "/PE1") (class "Default")
      (node (ref "IC3") (pin "3") (pinfunction "(TXD0)PE1_3") (pintype "bidirectional"))
      (node (ref "PWML") (pin "2") (pinfunction "2_2") (pintype "passive"))
      (node (ref "RN5") (pin "1") (pinfunction "1_1") (pintype "passive"))
    )
    (net (code "64") (name "/PE3") (class "Default")
      (node (ref "IC3") (pin "5") (pinfunction "(OC3A/AIN1)PE3_5") (pintype "bidirectional"))
      (node (ref "PWML") (pin "6") (pinfunction "6_6") (pintype "passive"))
    )
    (net (code "65") (name "/PE4") (class "Default")
      (node (ref "IC3") (pin "6") (pinfunction "(OC3B/INT4)PE4_6") (pintype "bidirectional"))
      (node (ref "PWML") (pin "3") (pinfunction "3_3") (pintype "passive"))
    )
    (net (code "66") (name "/PE5") (class "Default")
      (node (ref "IC3") (pin "7") (pinfunction "(OC3C/INT5)PE5_7") (pintype "bidirectional"))
      (node (ref "PWML") (pin "4") (pinfunction "4_4") (pintype "passive"))
    )
    (net (code "67") (name "/PE6") (class "Default")
      (node (ref "IC3") (pin "8") (pinfunction "(T3/INT6)PE6_8") (pintype "bidirectional"))
      (node (ref "SJ3") (pin "3") (pinfunction "2_3") (pintype "passive"))
    )
    (net (code "68") (name "/PG0") (class "Default")
      (node (ref "IC3") (pin "51") (pinfunction "(WR)PG0_51") (pintype "bidirectional"))
      (node (ref "XIO") (pin "22") (pinfunction "22_22") (pintype "passive"))
    )
    (net (code "69") (name "/PG1") (class "Default")
      (node (ref "IC3") (pin "52") (pinfunction "(RD)PG1_52") (pintype "bidirectional"))
      (node (ref "XIO") (pin "21") (pinfunction "21_21") (pintype "passive"))
    )
    (net (code "70") (name "/PG2") (class "Default")
      (node (ref "IC3") (pin "70") (pinfunction "(ALE)PG2_70") (pintype "bidirectional"))
      (node (ref "XIO") (pin "20") (pinfunction "20_20") (pintype "passive"))
    )
    (net (code "71") (name "/PG5") (class "Default")
      (node (ref "IC3") (pin "1") (pinfunction "(OC0B)PG5_1") (pintype "bidirectional"))
      (node (ref "PWML") (pin "5") (pinfunction "5_5") (pintype "passive"))
    )
    (net (code "72") (name "/PH3") (class "Default")
      (node (ref "IC3") (pin "15") (pinfunction "PH3(OC4A)_15") (pintype "bidirectional"))
      (node (ref "PWML") (pin "7") (pinfunction "7_7") (pintype "passive"))
    )
    (net (code "73") (name "/PH4") (class "Default")
      (node (ref "IC3") (pin "16") (pinfunction "PH4(OC4B)_16") (pintype "bidirectional"))
      (node (ref "PWML") (pin "8") (pinfunction "8_8") (pintype "passive"))
      (node (ref "SJ1") (pin "1") (pinfunction "1_1") (pintype "passive"))
    )
    (net (code "74") (name "/PH5") (class "Default")
      (node (ref "IC3") (pin "17") (pinfunction "PH5(OC4C)_17") (pintype "bidirectional"))
      (node (ref "JP1") (pin "10") (pinfunction "10_10") (pintype "passive"))
    )
    (net (code "75") (name "/PH6") (class "Default")
      (node (ref "IC3") (pin "18") (pinfunction "PH6(OC2B)_18") (pintype "bidirectional"))
      (node (ref "JP1") (pin "9") (pinfunction "9_9") (pintype "passive"))
    )
    (net (code "76") (name "/PH7") (class "Default")
      (node (ref "IC3") (pin "27") (pinfunction "PH7(T4)_27") (pintype "bidirectional"))
      (node (ref "SJ2") (pin "1") (pinfunction "1_1") (pintype "passive"))
    )
    (net (code "77") (name "/PJ2") (class "Default")
      (node (ref "IC3") (pin "65") (pinfunction "PJ2(XCK3/PCINT11)_65") (pintype "bidirectional"))
      (node (ref "SJ1") (pin "3") (pinfunction "2_3") (pintype "passive"))
    )
    (net (code "78") (name "/PJ6") (class "Default")
      (node (ref "IC3") (pin "69") (pinfunction "PJ6(PCINT15)_69") (pintype "bidirectional"))
      (node (ref "SJ3") (pin "1") (pinfunction "1_1") (pintype "passive"))
    )
    (net (code "79") (name "/PL0") (class "Default")
      (node (ref "IC3") (pin "35") (pinfunction "PL0(ICP4)_35") (pintype "bidirectional"))
      (node (ref "XIO") (pin "30") (pinfunction "30_30") (pintype "passive"))
    )
    (net (code "80") (name "/PL1") (class "Default")
      (node (ref "IC3") (pin "36") (pinfunction "PL1(ICP5)_36") (pintype "bidirectional"))
      (node (ref "XIO") (pin "29") (pinfunction "29_29") (pintype "passive"))
    )
    (net (code "81") (name "/PL2") (class "Default")
      (node (ref "IC3") (pin "37") (pinfunction "PL2(T5)_37") (pintype "bidirectional"))
      (node (ref "XIO") (pin "28") (pinfunction "28_28") (pintype "passive"))
    )
    (net (code "82") (name "/PL3") (class "Default")
      (node (ref "IC3") (pin "38") (pinfunction "PL3(OC5A)_38") (pintype "bidirectional"))
      (node (ref "XIO") (pin "27") (pinfunction "27_27") (pintype "passive"))
    )
    (net (code "83") (name "/PL4") (class "Default")
      (node (ref "IC3") (pin "39") (pinfunction "PL4(OC5B)_39") (pintype "bidirectional"))
      (node (ref "XIO") (pin "26") (pinfunction "26_26") (pintype "passive"))
    )
    (net (code "84") (name "/PL5") (class "Default")
      (node (ref "IC3") (pin "40") (pinfunction "PL5(OC5C)_40") (pintype "bidirectional"))
      (node (ref "XIO") (pin "25") (pinfunction "25_25") (pintype "passive"))
    )
    (net (code "85") (name "/PL6") (class "Default")
      (node (ref "IC3") (pin "41") (pinfunction "PL6_41") (pintype "bidirectional"))
      (node (ref "XIO") (pin "24") (pinfunction "24_24") (pintype "passive"))
    )
    (net (code "86") (name "/PL7") (class "Default")
      (node (ref "IC3") (pin "42") (pinfunction "PL7_42") (pintype "bidirectional"))
      (node (ref "XIO") (pin "23") (pinfunction "23_23") (pintype "passive"))
    )
    (net (code "87") (name "/RD+") (class "Default")
      (node (ref "IC4") (pin "29") (pinfunction "D+_29") (pintype "bidirectional"))
      (node (ref "RN4") (pin "4") (pinfunction "1_4") (pintype "passive"))
    )
    (net (code "88") (name "/RD-") (class "Default")
      (node (ref "IC4") (pin "30") (pinfunction "D-_30") (pintype "bidirectional"))
      (node (ref "RN4") (pin "1") (pinfunction "1_1") (pintype "passive"))
    )
    (net (code "89") (name "/RESET") (class "Default")
      (node (ref "C1") (pin "1") (pinfunction "1_1") (pintype "passive"))
      (node (ref "C10") (pin "2") (pinfunction "2_2") (pintype "passive"))
      (node (ref "D5") (pin "A") (pinfunction "A_A") (pintype "passive"))
      (node (ref "IC3") (pin "30") (pinfunction "RESET_30") (pintype "input"))
      (node (ref "ICSP") (pin "5") (pinfunction "5_5") (pintype "passive"))
      (node (ref "POWER") (pin "3") (pinfunction "3_3") (pintype "passive"))
      (node (ref "RESET") (pin "3") (pinfunction "3_3") (pintype "passive"))
      (node (ref "RESET") (pin "4") (pinfunction "4_4") (pintype "passive"))
      (node (ref "RESET-EN") (pin "1") (pinfunction "1_1") (pintype "passive"))
      (node (ref "RESET-EN") (pin "2") (pinfunction "2_2") (pintype "passive"))
      (node (ref "RN1") (pin "7") (pinfunction "2_7") (pintype "passive"))
    )
    (net (code "90") (name "/RESET2") (class "Default")
      (node (ref "D4") (pin "A") (pinfunction "A_A") (pintype "passive"))
      (node (ref "IC4") (pin "24") (pinfunction "RESET(PC1/DW)_24") (pintype "input"))
      (node (ref "ICSP1") (pin "5") (pinfunction "5_5") (pintype "passive"))
      (node (ref "RN3") (pin "8") (pinfunction "2_8") (pintype "passive"))
    )
    (net (code "91") (name "/RST_3V3") (class "Default")
      (node (ref "IC5") (pin "4") (pinfunction "O_4") (pintype "tri_state"))
      (node (ref "U7A") (pin "12") (pinfunction "RES_12") (pintype "bidirectional"))
    )
    (net (code "92") (name "/RST_5V") (class "Default")
      (node (ref "IC5") (pin "2") (pinfunction "I_2") (pintype "input"))
      (node (ref "RN6") (pin "4") (pinfunction "1_4") (pintype "passive"))
      (node (ref "SJ1") (pin "2") (pinfunction "C_2") (pintype "passive"))
    )
    (net (code "93") (name "/RXD1") (class "Default")
      (node (ref "COMMUNICATION") (pin "3") (pinfunction "3_3") (pintype "passive"))
      (node (ref "IC3") (pin "45") (pinfunction "(RXD1/INT2)PD2_45") (pintype "bidirectional"))
    )
    (net (code "94") (name "/RXD2") (class "Default")
      (node (ref "COMMUNICATION") (pin "5") (pinfunction "5_5") (pintype "passive"))
      (node (ref "IC3") (pin "12") (pinfunction "PH0(RXD2)_12") (pintype "bidirectional"))
    )
    (net (code "95") (name "/RXD3") (class "Default")
      (node (ref "COMMUNICATION") (pin "7") (pinfunction "7_7") (pintype "passive"))
      (node (ref "IC3") (pin "63") (pinfunction "PJ0(RXD3/PCINT9)_63") (pintype "bidirectional"))
    )
    (net (code "96") (name "/RXL") (class "Default")
      (node (ref "IC4") (pin "10") (pinfunction "(INT5/AIN3)PD4_10") (pintype "bidirectional"))
      (node (ref "RX") (pin "C") (pinfunction "C_C") (pintype "passive"))
    )
    (net (code "97") (name "/SCK2") (class "Default")
      (node (ref "IC4") (pin "15") (pinfunction "(SCLK/PCINT1)PB1_15") (pintype "bidirectional"))
      (node (ref "ICSP1") (pin "3") (pinfunction "3_3") (pintype "passive"))
    )
    (net (code "98") (name "/SCK_3V3") (class "Default")
      (node (ref "IC6") (pin "4") (pinfunction "O_4") (pintype "tri_state"))
      (node (ref "U7A") (pin "13") (pinfunction "SCK_13") (pintype "bidirectional"))
    )
    (net (code "99") (name "/SCL") (class "Default")
      (node (ref "COMMUNICATION") (pin "1") (pinfunction "1_1") (pintype "passive"))
      (node (ref "IC3") (pin "43") (pinfunction "(SCL/INT0)PD0_43") (pintype "bidirectional"))
      (node (ref "JP1") (pin "1") (pinfunction "1_1") (pintype "passive"))
      (node (ref "RN1") (pin "8") (pinfunction "2_8") (pintype "passive"))
    )
    (net (code "100") (name "/SDA") (class "Default")
      (node (ref "COMMUNICATION") (pin "2") (pinfunction "2_2") (pintype "passive"))
      (node (ref "IC3") (pin "44") (pinfunction "(SDA/INT1)PD1_44") (pintype "bidirectional"))
      (node (ref "JP1") (pin "2") (pinfunction "2_2") (pintype "passive"))
      (node (ref "RN1") (pin "3") (pinfunction "1_3") (pintype "passive"))
    )
    (net (code "101") (name "/SS_3V3") (class "Default")
      (node (ref "IC8") (pin "4") (pinfunction "O_4") (pintype "tri_state"))
      (node (ref "U7A") (pin "14") (pinfunction "SS_14") (pintype "bidirectional"))
    )
    (net (code "102") (name "/SS_MAX5") (class "Default")
      (node (ref "IC8") (pin "2") (pinfunction "I_2") (pintype "input"))
      (node (ref "RN6") (pin "2") (pinfunction "1_2") (pintype "passive"))
      (node (ref "SJ2") (pin "2") (pinfunction "C_2") (pintype "passive"))
    )
    (net (code "103") (name "/SW") (class "Default")
      (node (ref "C2") (pin "2") (pinfunction "2_2") (pintype "passive"))
      (node (ref "D3") (pin "P$1") (pinfunction "K_P$1") (pintype "bidirectional"))
      (node (ref "IC2") (pin "6") (pinfunction "SW_6") (pintype "output"))
      (node (ref "L1") (pin "P$1") (pinfunction "1_P$1") (pintype "passive"))
    )
    (net (code "104") (name "/TXD1") (class "Default")
      (node (ref "COMMUNICATION") (pin "4") (pinfunction "4_4") (pintype "passive"))
      (node (ref "IC3") (pin "46") (pinfunction "(TXD1/INT3)PD3_46") (pintype "bidirectional"))
    )
    (net (code "105") (name "/TXD2") (class "Default")
      (node (ref "COMMUNICATION") (pin "6") (pinfunction "6_6") (pintype "passive"))
      (node (ref "IC3") (pin "13") (pinfunction "PH1(TXD2)_13") (pintype "bidirectional"))
    )
    (net (code "106") (name "/TXD3") (class "Default")
      (node (ref "COMMUNICATION") (pin "8") (pinfunction "8_8") (pintype "passive"))
      (node (ref "IC3") (pin "64") (pinfunction "PJ1(TXD3/PCINT10)_64") (pintype "bidirectional"))
    )
    (net (code "107") (name "/TXL") (class "Default")
      (node (ref "IC4") (pin "11") (pinfunction "(XCK/AIN4/PCINT12)PD5_11") (pintype "bidirectional"))
      (node (ref "TX") (pin "C") (pinfunction "C_C") (pintype "passive"))
    )
    (net (code "108") (name "/UGND") (class "Default")
      (node (ref "C16") (pin "2") (pinfunction "2_2") (pintype "passive"))
      (node (ref "GROUND") (pin "1") (pinfunction "1_1") (pintype "passive"))
      (node (ref "IC4") (pin "28") (pinfunction "UGND_28") (pintype "power_in"))
      (node (ref "L2") (pin "1") (pinfunction "1_1") (pintype "passive"))
      (node (ref "X2") (pin "4") (pinfunction "4_4") (pintype "bidirectional"))
    )
    (net (code "109") (name "/USBVCC") (class "Default")
      (node (ref "C11") (pin "1") (pinfunction "1_1") (pintype "passive"))
      (node (ref "F1") (pin "1") (pinfunction "1_1") (pintype "passive"))
      (node (ref "IC4") (pin "31") (pinfunction "UVCC_31") (pintype "power_in"))
      (node (ref "T1") (pin "1") (pinfunction "D_1") (pintype "passive"))
    )
    (net (code "110") (name "/USHIELD") (class "Default")
      (node (ref "L2") (pin "2") (pinfunction "2_2") (pintype "passive"))
      (node (ref "X2") (pin "P$1") (pinfunction "P$1_P$1") (pintype "bidirectional"))
      (node (ref "X2") (pin "P$2") (pinfunction "P$2_P$2") (pintype "bidirectional"))
      (node (ref "X3") (pin "S1") (pinfunction "S1_S1") (pintype "passive"))
      (node (ref "X3") (pin "S2") (pinfunction "S2_S2") (pintype "passive"))
      (node (ref "Z1") (pin "1") (pinfunction "1_1") (pintype "passive"))
      (node (ref "Z2") (pin "1") (pinfunction "1_1") (pintype "passive"))
      (node (ref "Z3") (pin "1") (pinfunction "1_1") (pintype "passive"))
      (node (ref "Z4") (pin "1") (pinfunction "1_1") (pintype "passive"))
    )
    (net (code "111") (name "/VIN") (class "Default")
      (node (ref "C3") (pin "1") (pinfunction "1_1") (pintype "passive"))
      (node (ref "C4") (pin "+") (pinfunction "+_+") (pintype "passive"))
      (node (ref "D2") (pin "C") (pinfunction "C_C") (pintype "passive"))
      (node (ref "IC2") (pin "5") (pinfunction "VIN_5") (pintype "input"))
      (node (ref "PC1") (pin "+") (pinfunction "+_+") (pintype "passive"))
      (node (ref "POWER") (pin "8") (pinfunction "8_8") (pintype "passive"))
      (node (ref "R1") (pin "1") (pinfunction "1_1") (pintype "passive"))
      (node (ref "RN3") (pin "6") (pinfunction "2_6") (pintype "passive"))
      (node (ref "X1") (pin "2") (pinfunction "2_2") (pintype "power_in"))
    )
    (net (code "112") (name "/VUCAP") (class "Default")
      (node (ref "C16") (pin "1") (pinfunction "1_1") (pintype "passive"))
      (node (ref "IC4") (pin "27") (pinfunction "UCAP_27") (pintype "passive"))
    )
    (net (code "113") (name "/XT1") (class "Default")
      (node (ref "C13") (pin "1") (pinfunction "1_1") (pintype "passive"))
      (node (ref "IC4") (pin "1") (pinfunction "XTAL1_1") (pintype "bidirectional"))
      (node (ref "Y2") (pin "1") (pinfunction "C1_1") (pintype "passive"))
    )
    (net (code "114") (name "/XT2") (class "Default")
      (node (ref "C12") (pin "1") (pinfunction "1_1") (pintype "passive"))
      (node (ref "IC4") (pin "2") (pinfunction "XTAL2(PC0)_2") (pintype "bidirectional"))
      (node (ref "Y2") (pin "3") (pinfunction "C2_3") (pintype "passive"))
    )
    (net (code "115") (name "/XTAL1") (class "Default")
      (node (ref "IC3") (pin "34") (pinfunction "XTAL1_34") (pintype "input"))
      (node (ref "Y1") (pin "3") (pinfunction "3_3") (pintype "passive"))
    )
    (net (code "116") (name "/XTAL2") (class "Default")
      (node (ref "IC3") (pin "33") (pinfunction "XTAL2_33") (pintype "output"))
      (node (ref "Y1") (pin "1") (pinfunction "1_1") (pintype "passive"))
    )
    (net (code "117") (name "/XVCC") (class "Default")
      (node (ref "F1") (pin "2") (pinfunction "2_2") (pintype "passive"))
      (node (ref "X2") (pin "1") (pinfunction "1_1") (pintype "bidirectional"))
    )
    (net (code "118") (name "GND") (class "Default")
      (node (ref "C1") (pin "2") (pinfunction "2_2") (pintype "passive"))
      (node (ref "C11") (pin "2") (pinfunction "2_2") (pintype "passive"))
      (node (ref "C12") (pin "2") (pinfunction "2_2") (pintype "passive"))
      (node (ref "C13") (pin "2") (pinfunction "2_2") (pintype "passive"))
      (node (ref "C14") (pin "2") (pinfunction "2_2") (pintype "passive"))
      (node (ref "C15") (pin "2") (pinfunction "2_2") (pintype "passive"))
      (node (ref "C17") (pin "2") (pinfunction "2_2") (pintype "passive"))
      (node (ref "C18") (pin "2") (pinfunction "2_2") (pintype "passive"))
      (node (ref "C19") (pin "1") (pinfunction "1_1") (pintype "passive"))
      (node (ref "C20") (pin "1") (pinfunction "1_1") (pintype "passive"))
      (node (ref "C21") (pin "1") (pinfunction "1_1") (pintype "passive"))
      (node (ref "C22") (pin "1") (pinfunction "1_1") (pintype "passive"))
      (node (ref "C23") (pin "1") (pinfunction "1_1") (pintype "passive"))
      (node (ref "C24") (pin "2") (pinfunction "2_2") (pintype "passive"))
      (node (ref "C25") (pin "2") (pinfunction "2_2") (pintype "passive"))
      (node (ref "C26") (pin "2") (pinfunction "2_2") (pintype "passive"))
      (node (ref "C3") (pin "2") (pinfunction "2_2") (pintype "passive"))
      (node (ref "C4") (pin "-") (pinfunction "-_-") (pintype "passive"))
      (node (ref "C5") (pin "-") (pinfunction "-_-") (pintype "passive"))
      (node (ref "C6") (pin "2") (pinfunction "2_2") (pintype "passive"))
      (node (ref "C7") (pin "2") (pinfunction "2_2") (pintype "passive"))
      (node (ref "C8") (pin "2") (pinfunction "2_2") (pintype "passive"))
      (node (ref "C9") (pin "2") (pinfunction "2_2") (pintype "passive"))
      (node (ref "D2") (pin "A") (pinfunction "A_A") (pintype "passive"))
      (node (ref "D3") (pin "P$2") (pinfunction "A_P$2") (pintype "bidirectional"))
      (node (ref "GROUND") (pin "2") (pinfunction "2_2") (pintype "passive"))
      (node (ref "IC1") (pin "4") (pinfunction "V-_4") (pintype "power_in"))
      (node (ref "IC2") (pin "2") (pinfunction "GND_2") (pintype "power_in"))
      (node (ref "IC3") (pin "11") (pinfunction "GND_11") (pintype "power_in"))
      (node (ref "IC3") (pin "32") (pinfunction "GND1_32") (pintype "power_in"))
      (node (ref "IC3") (pin "62") (pinfunction "GND2_62") (pintype "power_in"))
      (node (ref "IC3") (pin "81") (pinfunction "GND3_81") (pintype "power_in"))
      (node (ref "IC3") (pin "99") (pinfunction "AGND_99") (pintype "power_in"))
      (node (ref "IC4") (pin "3") (pinfunction "GND_3") (pintype "power_in"))
      (node (ref "IC4") (pin "33") (pinfunction "PAD_33") (pintype "power_in"))
      (node (ref "IC5") (pin "1") (pinfunction "OE_1") (pintype "input"))
      (node (ref "IC5") (pin "3") (pinfunction "GND_3") (pintype "power_in"))
      (node (ref "IC6") (pin "1") (pinfunction "OE_1") (pintype "input"))
      (node (ref "IC6") (pin "3") (pinfunction "GND_3") (pintype "power_in"))
      (node (ref "IC7") (pin "2") (pinfunction "GND_2") (pintype "power_in"))
      (node (ref "IC8") (pin "1") (pinfunction "OE_1") (pintype "input"))
      (node (ref "IC8") (pin "3") (pinfunction "GND_3") (pintype "power_in"))
      (node (ref "IC9") (pin "1") (pinfunction "OE_1") (pintype "input"))
      (node (ref "IC9") (pin "3") (pinfunction "GND_3") (pintype "power_in"))
      (node (ref "ICSP") (pin "6") (pinfunction "6_6") (pintype "passive"))
      (node (ref "ICSP1") (pin "6") (pinfunction "6_6") (pintype "passive"))
      (node (ref "JP1") (pin "4") (pinfunction "4_4") (pintype "passive"))
      (node (ref "L") (pin "C") (pinfunction "C_C") (pintype "passive"))
      (node (ref "ON") (pin "C") (pinfunction "C_C") (pintype "passive"))
      (node (ref "PC1") (pin "-") (pinfunction "-_-") (pintype "passive"))
      (node (ref "POWER") (pin "6") (pinfunction "6_6") (pintype "passive"))
      (node (ref "POWER") (pin "7") (pinfunction "7_7") (pintype "passive"))
      (node (ref "R3") (pin "2") (pinfunction "2_2") (pintype "passive"))
      (node (ref "RESET") (pin "1") (pinfunction "1_1") (pintype "passive"))
      (node (ref "RESET") (pin "2") (pinfunction "2_2") (pintype "passive"))
      (node (ref "RN2") (pin "5") (pinfunction "2_5") (pintype "passive"))
      (node (ref "RN3") (pin "7") (pinfunction "2_7") (pintype "passive"))
      (node (ref "RN6") (pin "5") (pinfunction "2_5") (pintype "passive"))
      (node (ref "U7A") (pin "19") (pinfunction "GND_19") (pintype "bidirectional"))
      (node (ref "U7A") (pin "3") (pinfunction "GND_3") (pintype "bidirectional"))
      (node (ref "X1") (pin "1") (pinfunction "1_1") (pintype "power_in"))
      (node (ref "X1") (pin "3") (pinfunction "3_3") (pintype "power_in"))
      (node (ref "X3") (pin "4") (pinfunction "4_4") (pintype "passive"))
      (node (ref "XIO") (pin "35") (pinfunction "35_35") (pintype "passive"))
      (node (ref "XIO") (pin "36") (pinfunction "36_36") (pintype "passive"))
      (node (ref "Y1") (pin "2") (pinfunction "2_2") (pintype "passive"))
      (node (ref "Y2") (pin "2") (pinfunction "GND_2") (pintype "passive"))
      (node (ref "Y2") (pin "4") (pinfunction "GND_4") (pintype "passive"))
      (node (ref "Y3") (pin "2") (pinfunction "GND_2") (pintype "passive"))
      (node (ref "Y3") (pin "4") (pinfunction "GND_4") (pintype "passive"))
    )
    (net (code "119") (name "Net-(C17-Pad1)") (class "Default")
      (node (ref "C17") (pin "1") (pinfunction "1_1") (pintype "passive"))
      (node (ref "F2") (pin "1") (pinfunction "1_1") (pintype "passive"))
      (node (ref "L3") (pin "2") (pinfunction "2_2") (pintype "passive"))
    )
    (net (code "120") (name "Net-(F2-Pad2)") (class "Default")
      (node (ref "F2") (pin "2") (pinfunction "2_2") (pintype "passive"))
      (node (ref "X3") (pin "1") (pinfunction "1_1") (pintype "passive"))
    )
    (net (code "121") (name "Net-(RN2A-2)") (class "Default")
      (node (ref "L") (pin "A") (pinfunction "A_A") (pintype "passive"))
      (node (ref "RN2") (pin "8") (pinfunction "2_8") (pintype "passive"))
    )
    (net (code "122") (name "Net-(RN2B-2)") (class "Default")
      (node (ref "ON") (pin "A") (pinfunction "A_A") (pintype "passive"))
      (node (ref "RN2") (pin "7") (pinfunction "2_7") (pintype "passive"))
    )
    (net (code "123") (name "Net-(RN5C-1)") (class "Default")
      (node (ref "RN5") (pin "3") (pinfunction "1_3") (pintype "passive"))
      (node (ref "TX") (pin "A") (pinfunction "A_A") (pintype "passive"))
    )
    (net (code "124") (name "Net-(RN5D-1)") (class "Default")
      (node (ref "RN5") (pin "4") (pinfunction "1_4") (pintype "passive"))
      (node (ref "RX") (pin "A") (pinfunction "A_A") (pintype "passive"))
    )
    (net (code "125") (name "Net-(RN7-Pad1)") (class "Default")
      (node (ref "RN7") (pin "1") (pinfunction "1_1") (pintype "passive"))
      (node (ref "X3") (pin "2") (pinfunction "2_2") (pintype "passive"))
      (node (ref "Z4") (pin "2") (pinfunction "2_2") (pintype "passive"))
    )
    (net (code "126") (name "Net-(RN7A-2)") (class "Default")
      (node (ref "RN7") (pin "8") (pinfunction "2_8") (pintype "passive"))
      (node (ref "U7A") (pin "20") (pinfunction "D-_20") (pintype "bidirectional"))
    )
    (net (code "127") (name "Net-(RN7D-1)") (class "Default")
      (node (ref "RN7") (pin "4") (pinfunction "1_4") (pintype "passive"))
      (node (ref "X3") (pin "3") (pinfunction "3_3") (pintype "passive"))
      (node (ref "Z3") (pin "2") (pinfunction "2_2") (pintype "passive"))
    )
    (net (code "128") (name "Net-(RN7D-2)") (class "Default")
      (node (ref "RN7") (pin "5") (pinfunction "2_5") (pintype "passive"))
      (node (ref "U7A") (pin "21") (pinfunction "D+_21") (pintype "bidirectional"))
    )
    (net (code "129") (name "Net-(U7A-VBCOMP)") (class "Default")
      (node (ref "C24") (pin "1") (pinfunction "1_1") (pintype "passive"))
      (node (ref "U7A") (pin "22") (pinfunction "VBCOMP_22") (pintype "bidirectional"))
    )
    (net (code "130") (name "Net-(U7A-XI)") (class "Default")
      (node (ref "C20") (pin "2") (pinfunction "2_2") (pintype "passive"))
      (node (ref "U7A") (pin "24") (pinfunction "XI_24") (pintype "bidirectional"))
      (node (ref "Y3") (pin "1") (pinfunction "C1_1") (pintype "passive"))
    )
    (net (code "131") (name "Net-(U7A-XO)") (class "Default")
      (node (ref "C19") (pin "2") (pinfunction "2_2") (pintype "passive"))
      (node (ref "U7A") (pin "25") (pinfunction "XO_25") (pintype "bidirectional"))
      (node (ref "Y3") (pin "3") (pinfunction "C2_3") (pintype "passive"))
    )
    (net (code "132") (name "unconnected-(IC3-(CLKO{slash}ICP3{slash}INT7)PE7-Pad9)") (class "Default")
      (node (ref "IC3") (pin "9") (pinfunction "(CLKO/ICP3/INT7)PE7_9") (pintype "bidirectional"))
    )
    (net (code "133") (name "unconnected-(IC3-(ICP1)PD4-Pad47)") (class "Default")
      (node (ref "IC3") (pin "47") (pinfunction "(ICP1)PD4_47") (pintype "bidirectional"))
    )
    (net (code "134") (name "unconnected-(IC3-(T1)PD6-Pad49)") (class "Default")
      (node (ref "IC3") (pin "49") (pinfunction "(T1)PD6_49") (pintype "bidirectional"))
    )
    (net (code "135") (name "unconnected-(IC3-(TOSC1)PG4-Pad29)") (class "Default")
      (node (ref "IC3") (pin "29") (pinfunction "(TOSC1)PG4_29") (pintype "bidirectional"))
    )
    (net (code "136") (name "unconnected-(IC3-(TOSC2)PG3-Pad28)") (class "Default")
      (node (ref "IC3") (pin "28") (pinfunction "(TOSC2)PG3_28") (pintype "bidirectional"))
    )
    (net (code "137") (name "unconnected-(IC3-(XCK0{slash}AIN0)PE2-Pad4)") (class "Default")
      (node (ref "IC3") (pin "4") (pinfunction "(XCK0/AIN0)PE2_4") (pintype "bidirectional"))
    )
    (net (code "138") (name "unconnected-(IC3-(XCK1)PD5-Pad48)") (class "Default")
      (node (ref "IC3") (pin "48") (pinfunction "(XCK1)PD5_48") (pintype "bidirectional"))
    )
    (net (code "139") (name "unconnected-(IC3-PH2(XCK2)-Pad14)") (class "Default")
      (node (ref "IC3") (pin "14") (pinfunction "PH2(XCK2)_14") (pintype "bidirectional"))
    )
    (net (code "140") (name "unconnected-(IC3-PJ4(PCINT13)-Pad67)") (class "Default")
      (node (ref "IC3") (pin "67") (pinfunction "PJ4(PCINT13)_67") (pintype "bidirectional"))
    )
    (net (code "141") (name "unconnected-(IC3-PJ5(PCINT14)-Pad68)") (class "Default")
      (node (ref "IC3") (pin "68") (pinfunction "PJ5(PCINT14)_68") (pintype "bidirectional"))
    )
    (net (code "142") (name "unconnected-(IC3-PJ7-Pad79)") (class "Default")
      (node (ref "IC3") (pin "79") (pinfunction "PJ7_79") (pintype "bidirectional"))
    )
    (net (code "143") (name "unconnected-(IC4-(AIN0{slash}INT1)PD1-Pad7)") (class "Default")
      (node (ref "IC4") (pin "7") (pinfunction "(AIN0/INT1)PD1_7") (pintype "bidirectional"))
    )
    (net (code "144") (name "unconnected-(IC4-(AIN2{slash}PCINT11)PC2-Pad5)") (class "Default")
      (node (ref "IC4") (pin "5") (pinfunction "(AIN2/PCINT11)PC2_5") (pintype "bidirectional"))
    )
    (net (code "145") (name "unconnected-(IC4-(INT4{slash}ICP1{slash}CLK0)PC7-Pad22)") (class "Default")
      (node (ref "IC4") (pin "22") (pinfunction "(INT4/ICP1/CLK0)PC7_22") (pintype "bidirectional"))
    )
    (net (code "146") (name "unconnected-(IC4-(OC0B{slash}INT0)PD0-Pad6)") (class "Default")
      (node (ref "IC4") (pin "6") (pinfunction "(OC0B/INT0)PD0_6") (pintype "bidirectional"))
    )
    (net (code "147") (name "unconnected-(IC4-(OC1A{slash}PCINT8)PC6-Pad23)") (class "Default")
      (node (ref "IC4") (pin "23") (pinfunction "(OC1A/PCINT8)PC6_23") (pintype "bidirectional"))
    )
    (net (code "148") (name "unconnected-(IC4-(PCINT5)PB5-Pad19)") (class "Default")
      (node (ref "IC4") (pin "19") (pinfunction "(PCINT5)PB5_19") (pintype "bidirectional"))
    )
    (net (code "149") (name "unconnected-(IC4-(PCINT6)PB6-Pad20)") (class "Default")
      (node (ref "IC4") (pin "20") (pinfunction "(PCINT6)PB6_20") (pintype "bidirectional"))
    )
    (net (code "150") (name "unconnected-(IC4-(PCINT7{slash}OC0A{slash}OC1C)PB7-Pad21)") (class "Default")
      (node (ref "IC4") (pin "21") (pinfunction "(PCINT7/OC0A/OC1C)PB7_21") (pintype "bidirectional"))
    )
    (net (code "151") (name "unconnected-(IC4-(PCINT9{slash}OC1B)PC5-Pad25)") (class "Default")
      (node (ref "IC4") (pin "25") (pinfunction "(PCINT9/OC1B)PC5_25") (pintype "bidirectional"))
    )
    (net (code "152") (name "unconnected-(IC4-(PCINT10)PC4-Pad26)") (class "Default")
      (node (ref "IC4") (pin "26") (pinfunction "(PCINT10)PC4_26") (pintype "bidirectional"))
    )
    (net (code "153") (name "unconnected-(IC4-(RTS{slash}AIN5{slash}INT6)PD6-Pad12)") (class "Default")
      (node (ref "IC4") (pin "12") (pinfunction "(RTS/AIN5/INT6)PD6_12") (pintype "bidirectional"))
    )
    (net (code "154") (name "unconnected-(IC4-(SS{slash}PCINT0)PB0-Pad14)") (class "Default")
      (node (ref "IC4") (pin "14") (pinfunction "(SS/PCINT0)PB0_14") (pintype "bidirectional"))
    )
    (net (code "155") (name "unconnected-(IC4-(T1{slash}PCINT4)PB4-Pad18)") (class "Default")
      (node (ref "IC4") (pin "18") (pinfunction "(T1/PCINT4)PB4_18") (pintype "bidirectional"))
    )
    (net (code "156") (name "unconnected-(IC7-NC{slash}FB-Pad4)") (class "Default")
      (node (ref "IC7") (pin "4") (pinfunction "NC/FB_4") (pintype "passive"))
    )
    (net (code "157") (name "unconnected-(POWER-Pad1)") (class "Default")
      (node (ref "POWER") (pin "1") (pinfunction "1_1") (pintype "passive"))
    )
    (net (code "158") (name "unconnected-(R5-Pad1)") (class "Default")
      (node (ref "R5") (pin "1") (pinfunction "1_1") (pintype "passive"))
    )
    (net (code "159") (name "unconnected-(R5-Pad2)") (class "Default")
      (node (ref "R5") (pin "2") (pinfunction "2_2") (pintype "passive"))
    )
    (net (code "160") (name "unconnected-(R6-Pad1)") (class "Default")
      (node (ref "R6") (pin "1") (pinfunction "1_1") (pintype "passive"))
    )
    (net (code "161") (name "unconnected-(R6-Pad2)") (class "Default")
      (node (ref "R6") (pin "2") (pinfunction "2_2") (pintype "passive"))
    )
    (net (code "162") (name "unconnected-(R9-Pad1)") (class "Default")
      (node (ref "R9") (pin "1") (pinfunction "1_1") (pintype "passive"))
    )
    (net (code "163") (name "unconnected-(R9-Pad2)") (class "Default")
      (node (ref "R9") (pin "2") (pinfunction "2_2") (pintype "passive"))
    )
    (net (code "164") (name "unconnected-(RN1D-1-Pad4)") (class "Default")
      (node (ref "RN1") (pin "4") (pinfunction "1_4") (pintype "passive"))
    )
    (net (code "165") (name "unconnected-(RN1D-2-Pad5)") (class "Default")
      (node (ref "RN1") (pin "5") (pinfunction "2_5") (pintype "passive"))
    )
    (net (code "166") (name "unconnected-(RN3D-1-Pad4)") (class "Default")
      (node (ref "RN3") (pin "4") (pinfunction "1_4") (pintype "passive"))
    )
    (net (code "167") (name "unconnected-(RN3D-2-Pad5)") (class "Default")
      (node (ref "RN3") (pin "5") (pinfunction "2_5") (pintype "passive"))
    )
    (net (code "168") (name "unconnected-(RN4B-1-Pad2)") (class "Default")
      (node (ref "RN4") (pin "2") (pinfunction "1_2") (pintype "passive"))
    )
    (net (code "169") (name "unconnected-(RN4B-2-Pad7)") (class "Default")
      (node (ref "RN4") (pin "7") (pinfunction "2_7") (pintype "passive"))
    )
    (net (code "170") (name "unconnected-(RN4C-1-Pad3)") (class "Default")
      (node (ref "RN4") (pin "3") (pinfunction "1_3") (pintype "passive"))
    )
    (net (code "171") (name "unconnected-(RN4C-2-Pad6)") (class "Default")
      (node (ref "RN4") (pin "6") (pinfunction "2_6") (pintype "passive"))
    )
    (net (code "172") (name "unconnected-(RN6C-1-Pad3)") (class "Default")
      (node (ref "RN6") (pin "3") (pinfunction "1_3") (pintype "passive"))
    )
    (net (code "173") (name "unconnected-(RN6C-2-Pad6)") (class "Default")
      (node (ref "RN6") (pin "6") (pinfunction "2_6") (pintype "passive"))
    )
    (net (code "174") (name "unconnected-(RN7B-1-Pad2)") (class "Default")
      (node (ref "RN7") (pin "2") (pinfunction "1_2") (pintype "passive"))
    )
    (net (code "175") (name "unconnected-(RN7B-2-Pad7)") (class "Default")
      (node (ref "RN7") (pin "7") (pinfunction "2_7") (pintype "passive"))
    )
    (net (code "176") (name "unconnected-(RN7C-1-Pad3)") (class "Default")
      (node (ref "RN7") (pin "3") (pinfunction "1_3") (pintype "passive"))
    )
    (net (code "177") (name "unconnected-(RN7C-2-Pad6)") (class "Default")
      (node (ref "RN7") (pin "6") (pinfunction "2_6") (pintype "passive"))
    )
    (net (code "178") (name "unconnected-(U7A-GPIN0-Pad26)") (class "Default")
      (node (ref "U7A") (pin "26") (pinfunction "GPIN0_26") (pintype "bidirectional"))
    )
    (net (code "179") (name "unconnected-(U7A-GPIN1-Pad27)") (class "Default")
      (node (ref "U7A") (pin "27") (pinfunction "GPIN1_27") (pintype "bidirectional"))
    )
    (net (code "180") (name "unconnected-(U7A-GPIN2-Pad28)") (class "Default")
      (node (ref "U7A") (pin "28") (pinfunction "GPIN2_28") (pintype "bidirectional"))
    )
    (net (code "181") (name "unconnected-(U7A-GPIN3-Pad29)") (class "Default")
      (node (ref "U7A") (pin "29") (pinfunction "GPIN3_29") (pintype "bidirectional"))
    )
    (net (code "182") (name "unconnected-(U7A-GPIN4-Pad30)") (class "Default")
      (node (ref "U7A") (pin "30") (pinfunction "GPIN4_30") (pintype "bidirectional"))
    )
    (net (code "183") (name "unconnected-(U7A-GPIN5-Pad31)") (class "Default")
      (node (ref "U7A") (pin "31") (pinfunction "GPIN5_31") (pintype "bidirectional"))
    )
    (net (code "184") (name "unconnected-(U7A-GPIN6-Pad32)") (class "Default")
      (node (ref "U7A") (pin "32") (pinfunction "GPIN6_32") (pintype "bidirectional"))
    )
    (net (code "185") (name "unconnected-(U7A-GPIN7-Pad1)") (class "Default")
      (node (ref "U7A") (pin "1") (pinfunction "GPIN7_1") (pintype "bidirectional"))
    )
    (net (code "186") (name "unconnected-(U7A-GPOUT0-Pad4)") (class "Default")
      (node (ref "U7A") (pin "4") (pinfunction "GPOUT0_4") (pintype "bidirectional"))
    )
    (net (code "187") (name "unconnected-(U7A-GPOUT1-Pad5)") (class "Default")
      (node (ref "U7A") (pin "5") (pinfunction "GPOUT1_5") (pintype "bidirectional"))
    )
    (net (code "188") (name "unconnected-(U7A-GPOUT2-Pad6)") (class "Default")
      (node (ref "U7A") (pin "6") (pinfunction "GPOUT2_6") (pintype "bidirectional"))
    )
    (net (code "189") (name "unconnected-(U7A-GPOUT3-Pad7)") (class "Default")
      (node (ref "U7A") (pin "7") (pinfunction "GPOUT3_7") (pintype "bidirectional"))
    )
    (net (code "190") (name "unconnected-(U7A-GPOUT4-Pad8)") (class "Default")
      (node (ref "U7A") (pin "8") (pinfunction "GPOUT4_8") (pintype "bidirectional"))
    )
    (net (code "191") (name "unconnected-(U7A-GPOUT5-Pad9)") (class "Default")
      (node (ref "U7A") (pin "9") (pinfunction "GPOUT5_9") (pintype "bidirectional"))
    )
    (net (code "192") (name "unconnected-(U7A-GPOUT6-Pad10)") (class "Default")
      (node (ref "U7A") (pin "10") (pinfunction "GPOUT6_10") (pintype "bidirectional"))
    )
    (net (code "193") (name "unconnected-(U7A-GPOUT7-Pad11)") (class "Default")
      (node (ref "U7A") (pin "11") (pinfunction "GPOUT7_11") (pintype "bidirectional"))
    )
  )
)
